# d-cube.net
KiCad netlist of a schematic drawn in EAGLE
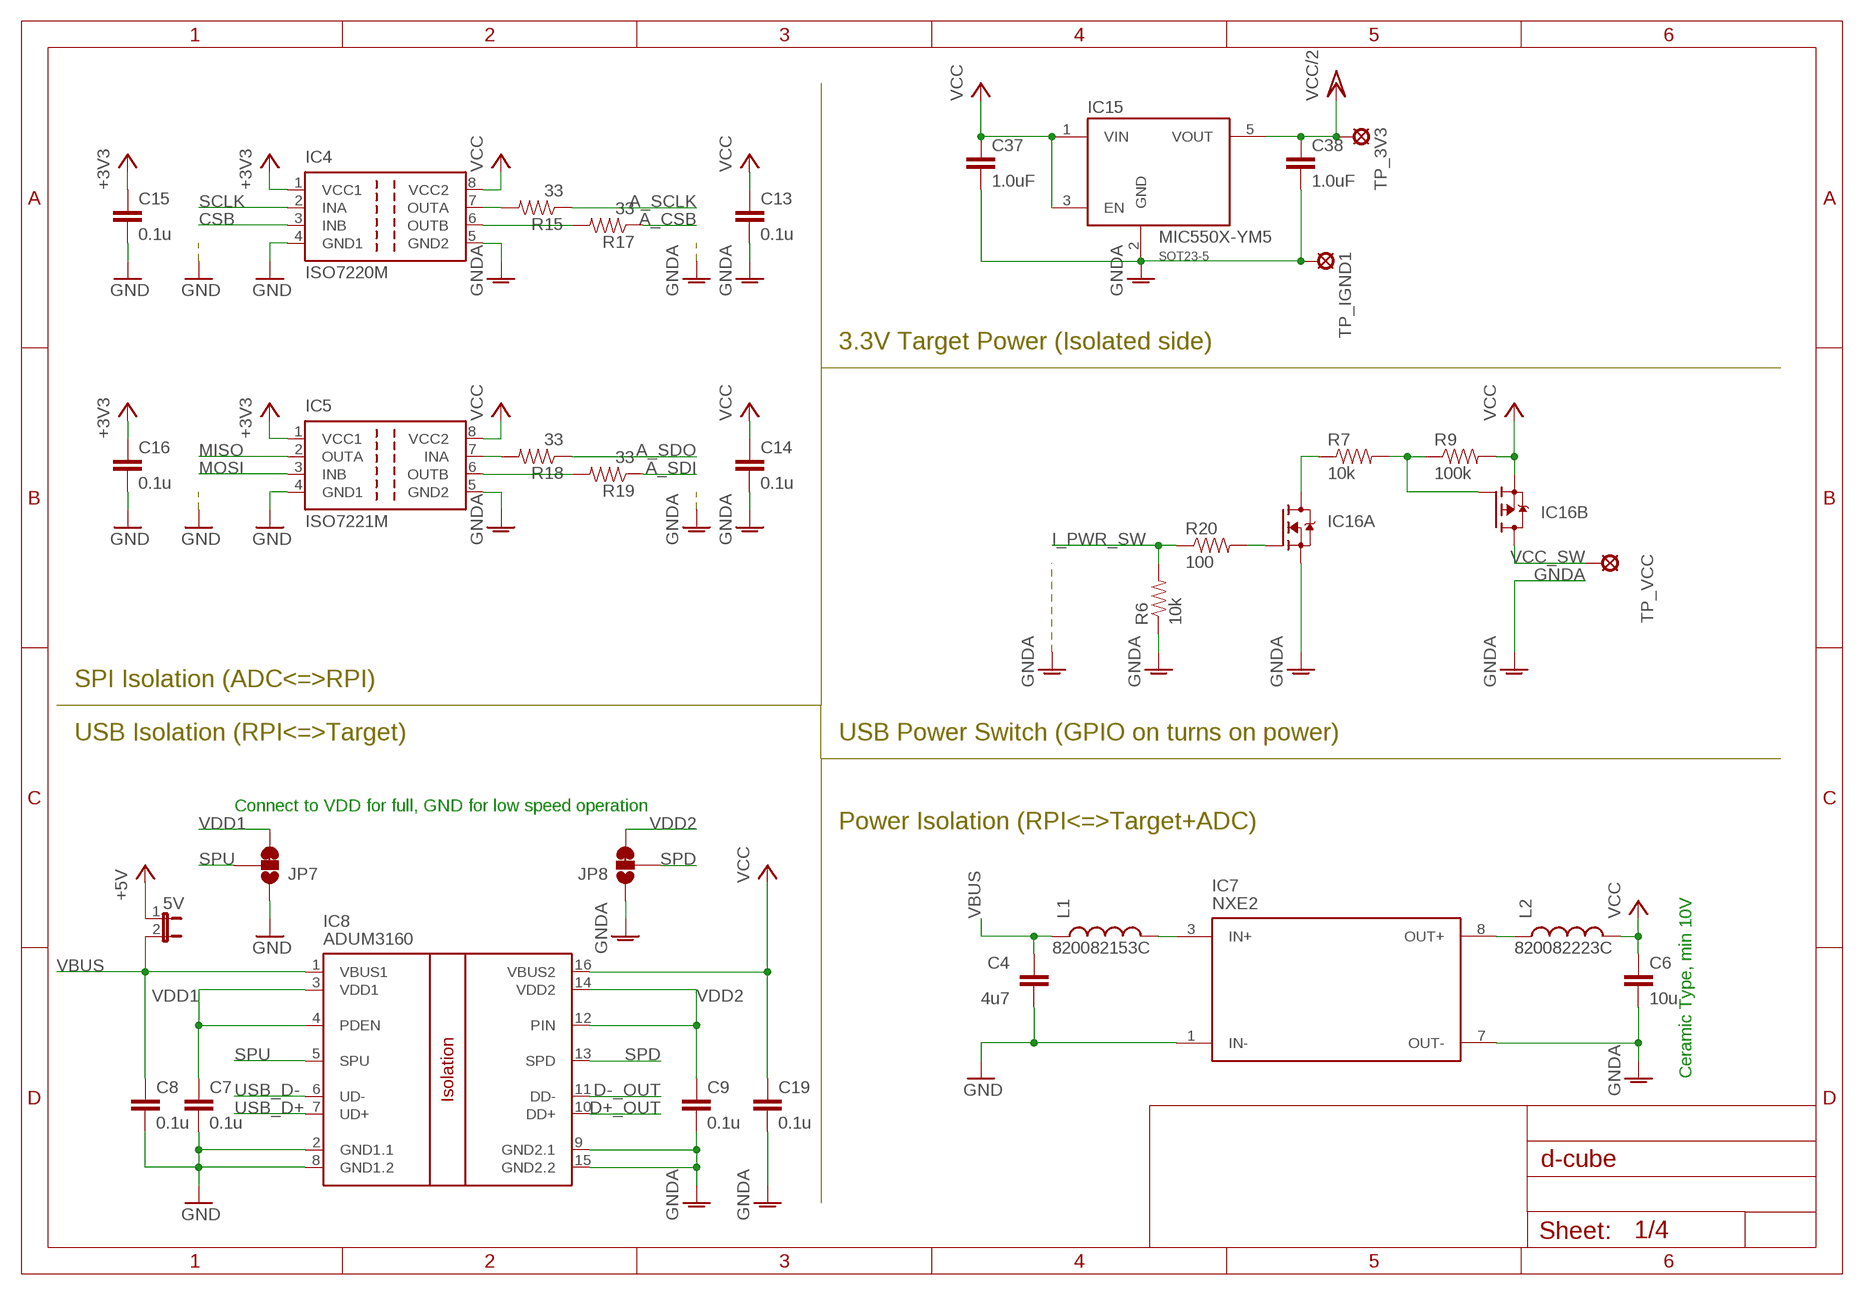
[diagram p0: schematic, sheet 1]
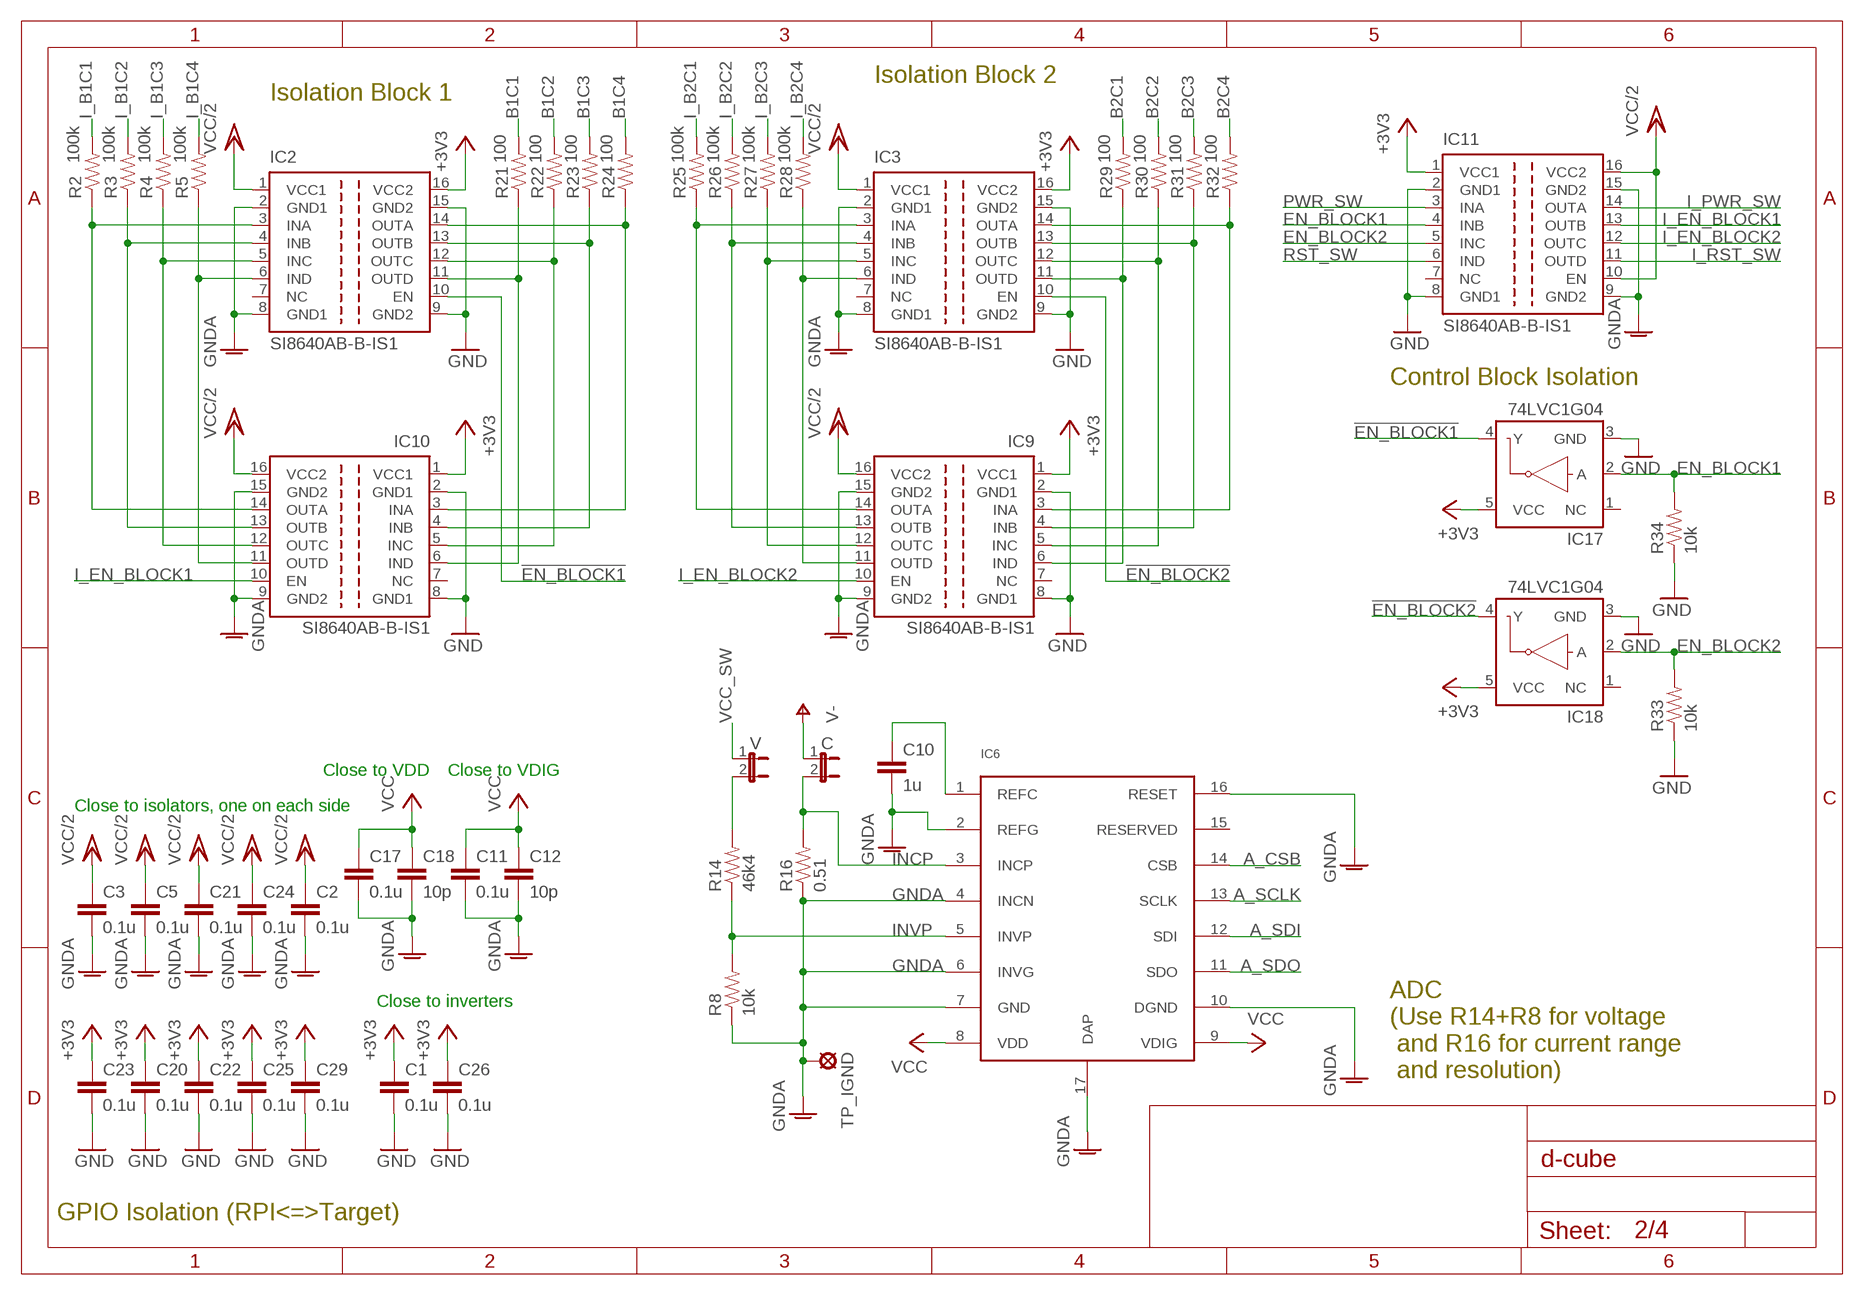
[diagram p1: schematic, sheet 2]
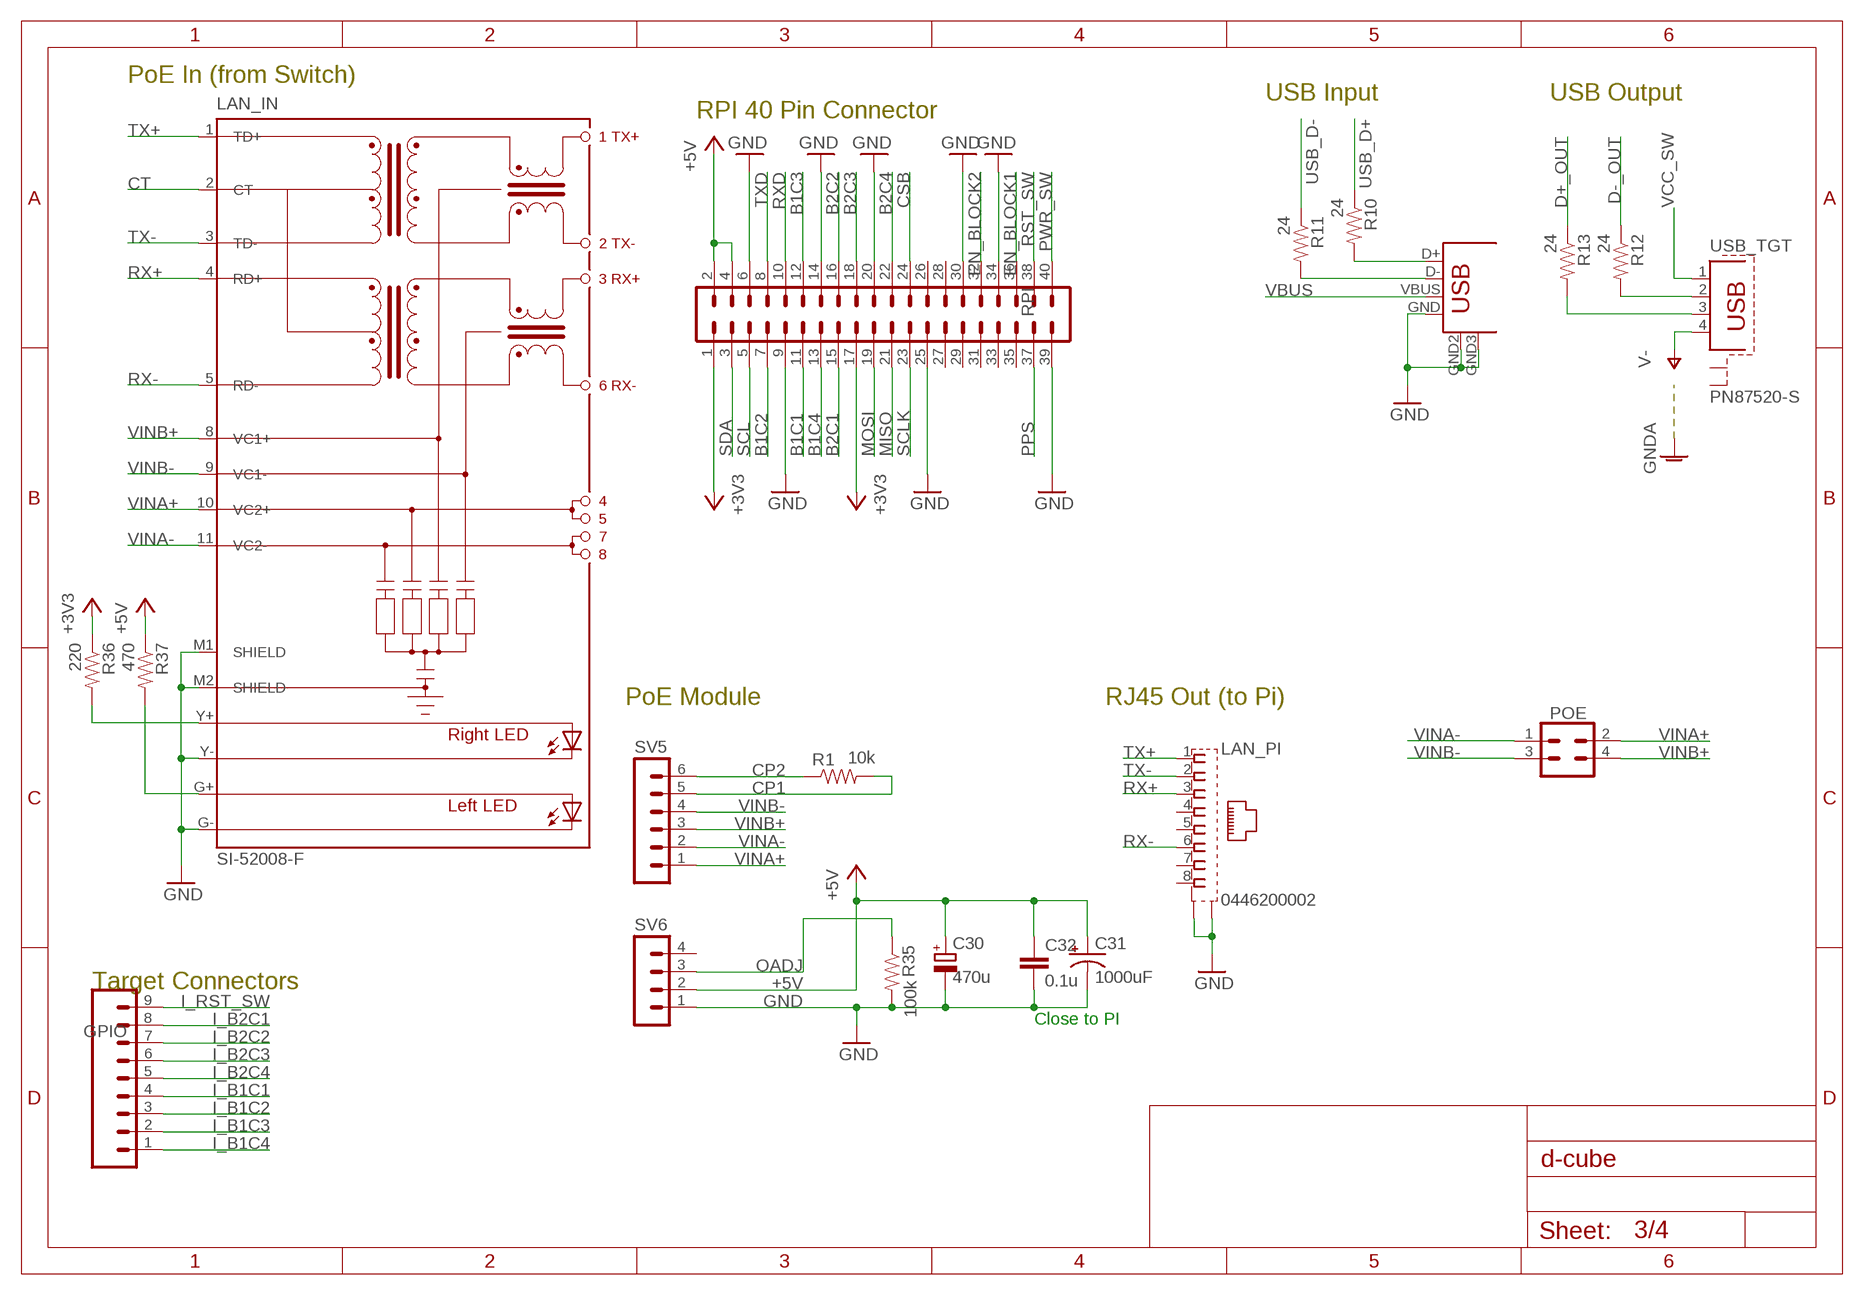
[diagram p2: schematic, sheet 3]
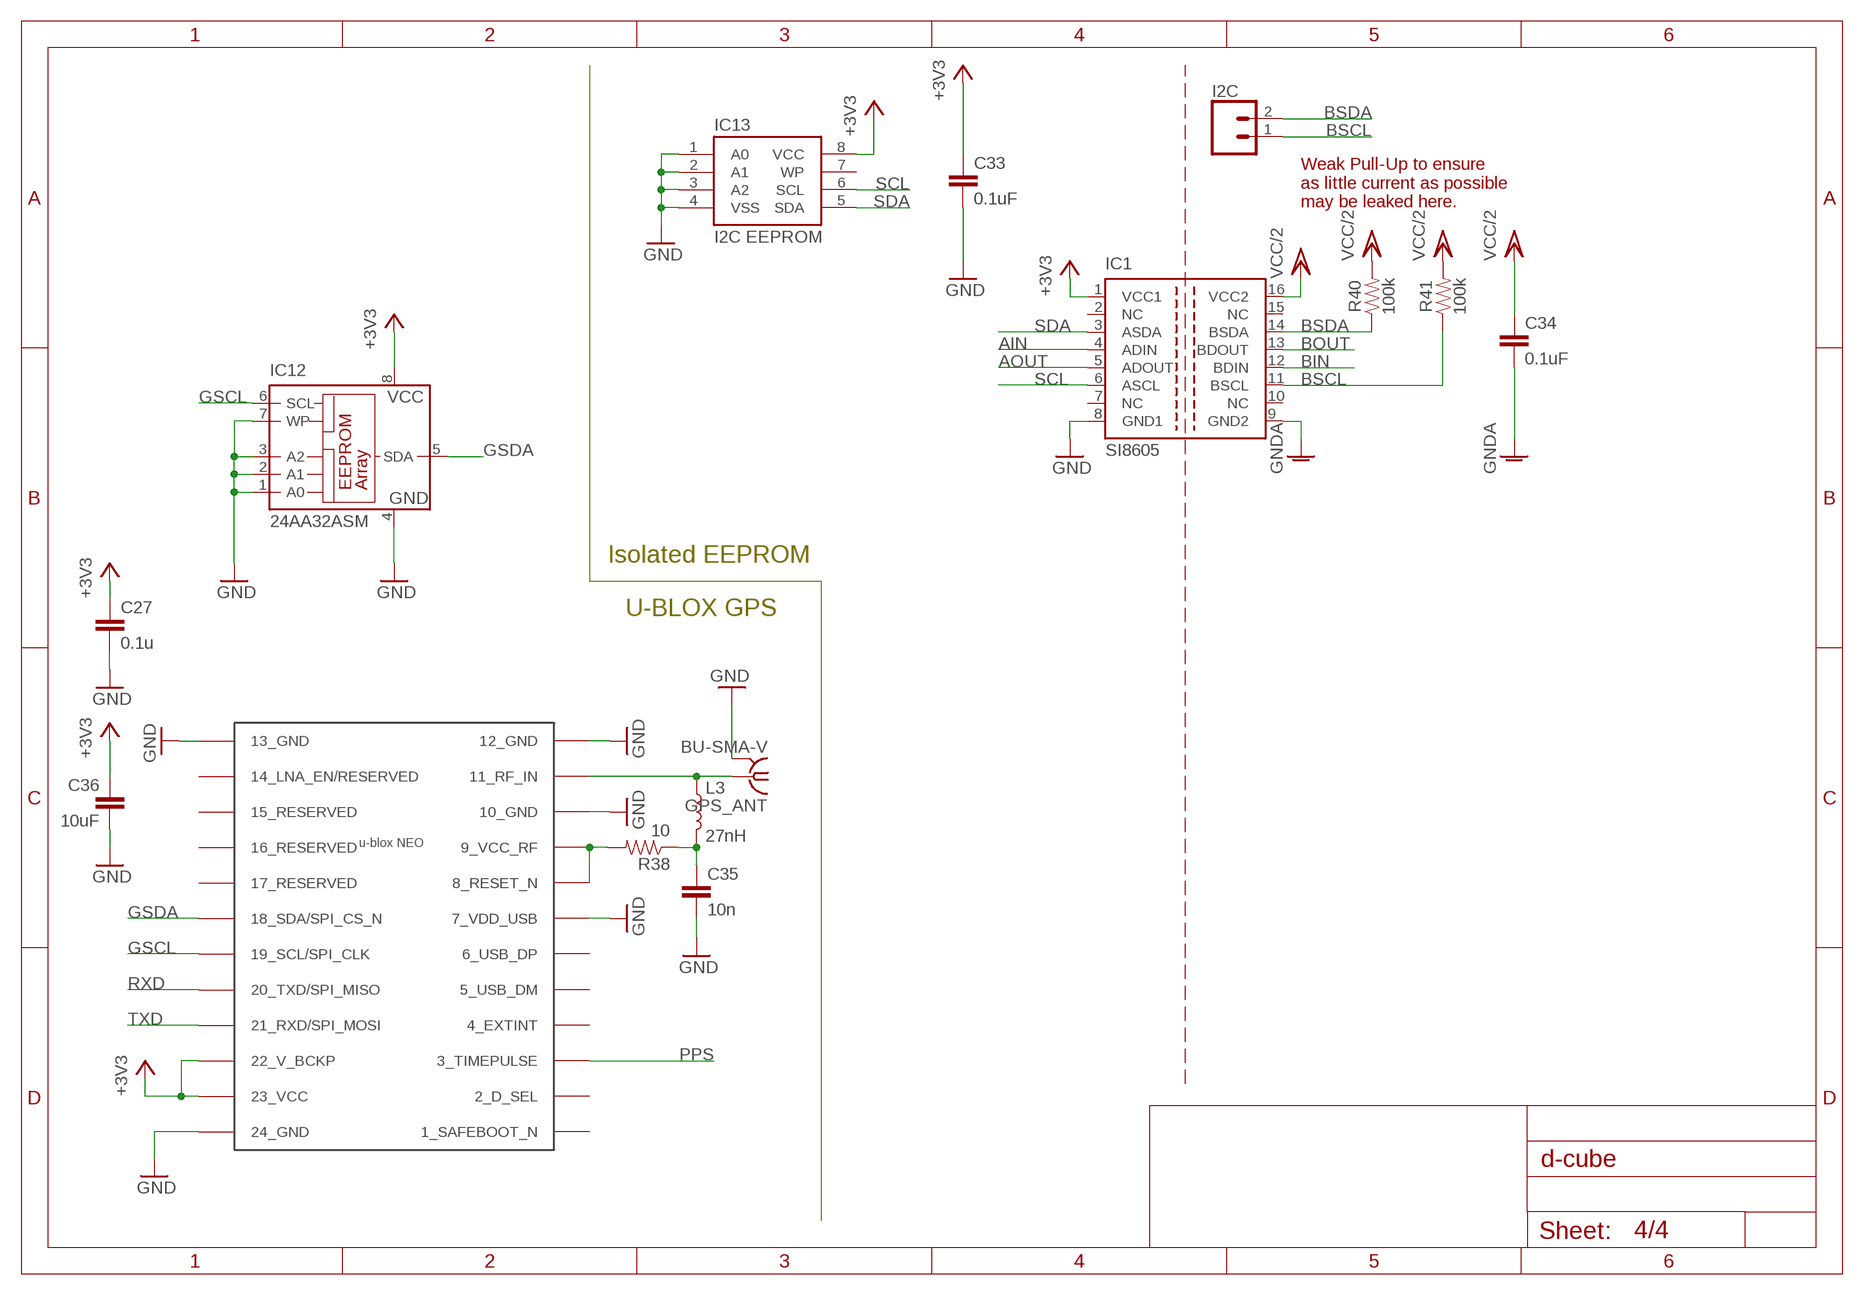
[diagram p3: schematic, sheet 4]

(export (version "E")
  (design (tool "Eeschema 10.0.6"))
  (components
    (comp (ref "C")
      (value "JP1E")
      (footprint "eagle-import:JP1")
      (libsource (lib "eagle-import") (part "JP1E"))
    )
    (comp (ref "C1")
      (value "0.1u")
      (footprint "eagle-import:0402-CAP")
      (libsource (lib "eagle-import") (part "CAP0402-CAP"))
    )
    (comp (ref "C2")
      (value "0.1u")
      (footprint "eagle-import:0402-CAP")
      (libsource (lib "eagle-import") (part "CAP0402-CAP"))
    )
    (comp (ref "C3")
      (value "0.1u")
      (footprint "eagle-import:0402-CAP")
      (libsource (lib "eagle-import") (part "CAP0402-CAP"))
    )
    (comp (ref "C5")
      (value "0.1u")
      (footprint "eagle-import:0402-CAP")
      (libsource (lib "eagle-import") (part "CAP0402-CAP"))
    )
    (comp (ref "C10")
      (value "1u")
      (footprint "eagle-import:0402-CAP")
      (libsource (lib "eagle-import") (part "CAP0402-CAP"))
    )
    (comp (ref "C11")
      (value "0.1u")
      (footprint "eagle-import:0402-CAP")
      (libsource (lib "eagle-import") (part "CAP0402-CAP"))
    )
    (comp (ref "C12")
      (value "10p")
      (footprint "eagle-import:0402-CAP")
      (libsource (lib "eagle-import") (part "CAP0402-CAP"))
    )
    (comp (ref "C17")
      (value "0.1u")
      (footprint "eagle-import:0402-CAP")
      (libsource (lib "eagle-import") (part "CAP0402-CAP"))
    )
    (comp (ref "C18")
      (value "10p")
      (footprint "eagle-import:0402-CAP")
      (libsource (lib "eagle-import") (part "CAP0402-CAP"))
    )
    (comp (ref "C20")
      (value "0.1u")
      (footprint "eagle-import:0402-CAP")
      (libsource (lib "eagle-import") (part "CAP0402-CAP"))
    )
    (comp (ref "C21")
      (value "0.1u")
      (footprint "eagle-import:0402-CAP")
      (libsource (lib "eagle-import") (part "CAP0402-CAP"))
    )
    (comp (ref "C22")
      (value "0.1u")
      (footprint "eagle-import:0402-CAP")
      (libsource (lib "eagle-import") (part "CAP0402-CAP"))
    )
    (comp (ref "C23")
      (value "0.1u")
      (footprint "eagle-import:0402-CAP")
      (libsource (lib "eagle-import") (part "CAP0402-CAP"))
    )
    (comp (ref "C24")
      (value "0.1u")
      (footprint "eagle-import:0402-CAP")
      (libsource (lib "eagle-import") (part "CAP0402-CAP"))
    )
    (comp (ref "C25")
      (value "0.1u")
      (footprint "eagle-import:0402-CAP")
      (libsource (lib "eagle-import") (part "CAP0402-CAP"))
    )
    (comp (ref "C26")
      (value "0.1u")
      (footprint "eagle-import:0402-CAP")
      (libsource (lib "eagle-import") (part "CAP0402-CAP"))
    )
    (comp (ref "C29")
      (value "0.1u")
      (footprint "eagle-import:0402-CAP")
      (libsource (lib "eagle-import") (part "CAP0402-CAP"))
    )
    (comp (ref "IC2")
      (value "SI8640AB-B-IS1")
      (footprint "eagle-import:SO-16")
      (libsource (lib "eagle-import") (part "SI8640AB-B-IS1"))
    )
    (comp (ref "IC3")
      (value "SI8640AB-B-IS1")
      (footprint "eagle-import:SO-16")
      (libsource (lib "eagle-import") (part "SI8640AB-B-IS1"))
    )
    (comp (ref "IC6")
      (value "LMP92064")
      (footprint "eagle-import:WSON-16")
      (libsource (lib "eagle-import") (part "LMP92064"))
    )
    (comp (ref "IC9")
      (value "SI8640AB-B-IS1")
      (footprint "eagle-import:SO-16")
      (libsource (lib "eagle-import") (part "SI8640AB-B-IS1"))
    )
    (comp (ref "IC10")
      (value "SI8640AB-B-IS1")
      (footprint "eagle-import:SO-16")
      (libsource (lib "eagle-import") (part "SI8640AB-B-IS1"))
    )
    (comp (ref "IC11")
      (value "SI8640AB-B-IS1")
      (footprint "eagle-import:SO-16")
      (libsource (lib "eagle-import") (part "SI8640AB-B-IS1"))
    )
    (comp (ref "IC17")
      (value "74LVC1G04")
      (footprint "eagle-import:SOT353")
      (libsource (lib "eagle-import") (part "INVERTER_SOT353-5"))
    )
    (comp (ref "IC18")
      (value "74LVC1G04")
      (footprint "eagle-import:SOT353")
      (libsource (lib "eagle-import") (part "INVERTER_SOT353-5"))
    )
    (comp (ref "R2")
      (value "100k")
      (footprint "eagle-import:0402-RES")
      (libsource (lib "eagle-import") (part "RESISTOR0402-RES"))
    )
    (comp (ref "R3")
      (value "100k")
      (footprint "eagle-import:0402-RES")
      (libsource (lib "eagle-import") (part "RESISTOR0402-RES"))
    )
    (comp (ref "R4")
      (value "100k")
      (footprint "eagle-import:0402-RES")
      (libsource (lib "eagle-import") (part "RESISTOR0402-RES"))
    )
    (comp (ref "R5")
      (value "100k")
      (footprint "eagle-import:0402-RES")
      (libsource (lib "eagle-import") (part "RESISTOR0402-RES"))
    )
    (comp (ref "R8")
      (value "10k")
      (footprint "eagle-import:0805")
      (libsource (lib "eagle-import") (part "RESISTOR0805-RES"))
    )
    (comp (ref "R14")
      (value "46k4")
      (footprint "eagle-import:0805")
      (libsource (lib "eagle-import") (part "RESISTOR0805-RES"))
    )
    (comp (ref "R16")
      (value "0.51")
      (footprint "eagle-import:1206")
      (libsource (lib "eagle-import") (part "RESISTOR1206"))
    )
    (comp (ref "R21")
      (value "100")
      (footprint "eagle-import:0402-RES")
      (libsource (lib "eagle-import") (part "RESISTOR0402-RES"))
    )
    (comp (ref "R22")
      (value "100")
      (footprint "eagle-import:0402-RES")
      (libsource (lib "eagle-import") (part "RESISTOR0402-RES"))
    )
    (comp (ref "R23")
      (value "100")
      (footprint "eagle-import:0402-RES")
      (libsource (lib "eagle-import") (part "RESISTOR0402-RES"))
    )
    (comp (ref "R24")
      (value "100")
      (footprint "eagle-import:0402-RES")
      (libsource (lib "eagle-import") (part "RESISTOR0402-RES"))
    )
    (comp (ref "R25")
      (value "100k")
      (footprint "eagle-import:0402-RES")
      (libsource (lib "eagle-import") (part "RESISTOR0402-RES"))
    )
    (comp (ref "R26")
      (value "100k")
      (footprint "eagle-import:0402-RES")
      (libsource (lib "eagle-import") (part "RESISTOR0402-RES"))
    )
    (comp (ref "R27")
      (value "100k")
      (footprint "eagle-import:0402-RES")
      (libsource (lib "eagle-import") (part "RESISTOR0402-RES"))
    )
    (comp (ref "R28")
      (value "100k")
      (footprint "eagle-import:0402-RES")
      (libsource (lib "eagle-import") (part "RESISTOR0402-RES"))
    )
    (comp (ref "R29")
      (value "100")
      (footprint "eagle-import:0402-RES")
      (libsource (lib "eagle-import") (part "RESISTOR0402-RES"))
    )
    (comp (ref "R30")
      (value "100")
      (footprint "eagle-import:0402-RES")
      (libsource (lib "eagle-import") (part "RESISTOR0402-RES"))
    )
    (comp (ref "R31")
      (value "100")
      (footprint "eagle-import:0402-RES")
      (libsource (lib "eagle-import") (part "RESISTOR0402-RES"))
    )
    (comp (ref "R32")
      (value "100")
      (footprint "eagle-import:0402-RES")
      (libsource (lib "eagle-import") (part "RESISTOR0402-RES"))
    )
    (comp (ref "R33")
      (value "10k")
      (footprint "eagle-import:0402-RES")
      (libsource (lib "eagle-import") (part "RESISTOR0402-RES"))
    )
    (comp (ref "R34")
      (value "10k")
      (footprint "eagle-import:0402-RES")
      (libsource (lib "eagle-import") (part "RESISTOR0402-RES"))
    )
    (comp (ref "TP_IGND")
      (value "LSP10")
      (footprint "eagle-import:LSP10")
      (libsource (lib "eagle-import") (part "LSP10"))
    )
    (comp (ref "V")
      (value "JP1E")
      (footprint "eagle-import:JP1")
      (libsource (lib "eagle-import") (part "JP1E"))
    )
    (comp (ref "5V")
      (value "JP1E")
      (footprint "eagle-import:JP1")
      (libsource (lib "eagle-import") (part "JP1E"))
    )
    (comp (ref "C4")
      (value "4u7")
      (footprint "eagle-import:0805")
      (libsource (lib "eagle-import") (part "CAP0805"))
    )
    (comp (ref "C6")
      (value "10u")
      (footprint "eagle-import:0805")
      (libsource (lib "eagle-import") (part "CAP0805"))
    )
    (comp (ref "C7")
      (value "0.1u")
      (footprint "eagle-import:0402-CAP")
      (libsource (lib "eagle-import") (part "CAP0402-CAP"))
    )
    (comp (ref "C8")
      (value "0.1u")
      (footprint "eagle-import:0402-CAP")
      (libsource (lib "eagle-import") (part "CAP0402-CAP"))
    )
    (comp (ref "C9")
      (value "0.1u")
      (footprint "eagle-import:0402-CAP")
      (libsource (lib "eagle-import") (part "CAP0402-CAP"))
    )
    (comp (ref "C13")
      (value "0.1u")
      (footprint "eagle-import:0402-CAP")
      (libsource (lib "eagle-import") (part "CAP0402-CAP"))
    )
    (comp (ref "C14")
      (value "0.1u")
      (footprint "eagle-import:0402-CAP")
      (libsource (lib "eagle-import") (part "CAP0402-CAP"))
    )
    (comp (ref "C15")
      (value "0.1u")
      (footprint "eagle-import:0402-CAP")
      (libsource (lib "eagle-import") (part "CAP0402-CAP"))
    )
    (comp (ref "C16")
      (value "0.1u")
      (footprint "eagle-import:0402-CAP")
      (libsource (lib "eagle-import") (part "CAP0402-CAP"))
    )
    (comp (ref "C19")
      (value "0.1u")
      (footprint "eagle-import:0402-CAP")
      (libsource (lib "eagle-import") (part "CAP0402-CAP"))
    )
    (comp (ref "C37")
      (value "1.0uF")
      (footprint "eagle-import:0805")
      (libsource (lib "eagle-import") (part "1.0UF-0805-25V-10%"))
    )
    (comp (ref "C38")
      (value "1.0uF")
      (footprint "eagle-import:0805")
      (libsource (lib "eagle-import") (part "1.0UF-0805-25V-10%"))
    )
    (comp (ref "IC4")
      (value "ISO7220M")
      (footprint "eagle-import:SO-08")
      (fields (field (name "MPN") "ISO7220MD"))
      (libsource (lib "eagle-import") (part "ISO7220M"))
    )
    (comp (ref "IC5")
      (value "ISO7221M")
      (footprint "eagle-import:SO-08")
      (fields (field (name "MPN") "ISO7221MD"))
      (libsource (lib "eagle-import") (part "ISO7221M"))
    )
    (comp (ref "IC7")
      (value "NXE2")
      (footprint "eagle-import:NXE2")
      (libsource (lib "eagle-import") (part "NXE2"))
    )
    (comp (ref "IC8")
      (value "ADUM3160")
      (footprint "eagle-import:SO-16W")
      (libsource (lib "eagle-import") (part "ADUM3160"))
    )
    (comp (ref "IC15")
      (value "MIC550X-YM5")
      (footprint "eagle-import:SOT23-5-DBV")
      (fields (field (name "PACKAGE") "SOT23-5"))
      (libsource (lib "eagle-import") (part "MIC550X-YM5"))
    )
    (comp (ref "IC16")
      (value "COMPLEMENTARY")
      (footprint "eagle-import:SOT-363")
      (libsource (lib "eagle-import") (part "COMPLEMENTARY"))
    )
    (comp (ref "JP7")
      (value "JUMPER-PAD-3-2OF3_NC_BY_TRACE_LARGE")
      (footprint "eagle-import:PAD-JUMPER-3-2OF3_NC_BY_TRACE_YES_SILK_LARGE")
      (libsource (lib "eagle-import") (part "JUMPER-PAD-3-2OF3_NC_BY_TRACE_LARGE"))
    )
    (comp (ref "JP8")
      (value "JUMPER-PAD-3-2OF3_NC_BY_TRACE_LARGE")
      (footprint "eagle-import:PAD-JUMPER-3-2OF3_NC_BY_TRACE_YES_SILK_LARGE")
      (libsource (lib "eagle-import") (part "JUMPER-PAD-3-2OF3_NC_BY_TRACE_LARGE"))
    )
    (comp (ref "L1")
      (value "820082153C")
      (footprint "eagle-import:8200")
      (libsource (lib "eagle-import") (part "820082153C"))
    )
    (comp (ref "L2")
      (value "820082223C")
      (footprint "eagle-import:8200")
      (libsource (lib "eagle-import") (part "820082223C"))
    )
    (comp (ref "R6")
      (value "10k")
      (footprint "eagle-import:0402-RES")
      (libsource (lib "eagle-import") (part "RESISTOR0402-RES"))
    )
    (comp (ref "R7")
      (value "10k")
      (footprint "eagle-import:0402-RES")
      (libsource (lib "eagle-import") (part "RESISTOR0402-RES"))
    )
    (comp (ref "R9")
      (value "100k")
      (footprint "eagle-import:0402-RES")
      (libsource (lib "eagle-import") (part "RESISTOR0402-RES"))
    )
    (comp (ref "R15")
      (value "33")
      (footprint "eagle-import:0402-RES")
      (libsource (lib "eagle-import") (part "RESISTOR0402-RES"))
    )
    (comp (ref "R17")
      (value "33")
      (footprint "eagle-import:0402-RES")
      (libsource (lib "eagle-import") (part "RESISTOR0402-RES"))
    )
    (comp (ref "R18")
      (value "33")
      (footprint "eagle-import:0402-RES")
      (libsource (lib "eagle-import") (part "RESISTOR0402-RES"))
    )
    (comp (ref "R19")
      (value "33")
      (footprint "eagle-import:0402-RES")
      (libsource (lib "eagle-import") (part "RESISTOR0402-RES"))
    )
    (comp (ref "R20")
      (value "100")
      (footprint "eagle-import:0402-RES")
      (libsource (lib "eagle-import") (part "RESISTOR0402-RES"))
    )
    (comp (ref "TP_3V3")
      (value "LSP10")
      (footprint "eagle-import:LSP10")
      (libsource (lib "eagle-import") (part "LSP10"))
    )
    (comp (ref "TP_IGND1")
      (value "LSP10")
      (footprint "eagle-import:LSP10")
      (libsource (lib "eagle-import") (part "LSP10"))
    )
    (comp (ref "TP_VCC")
      (value "LSP10")
      (footprint "eagle-import:LSP10")
      (libsource (lib "eagle-import") (part "LSP10"))
    )
    (comp (ref "C27")
      (value "0.1u")
      (footprint "eagle-import:0402-CAP")
      (libsource (lib "eagle-import") (part "CAP0402-CAP"))
    )
    (comp (ref "C33")
      (value "0.1uF")
      (footprint "eagle-import:0402")
      (libsource (lib "eagle-import") (part "0.1UF-0402-16V-10%"))
    )
    (comp (ref "C34")
      (value "0.1uF")
      (footprint "eagle-import:0402")
      (libsource (lib "eagle-import") (part "0.1UF-0402-16V-10%"))
    )
    (comp (ref "C35")
      (value "10n")
      (footprint "eagle-import:0805")
      (libsource (lib "eagle-import") (part "CAP0805"))
    )
    (comp (ref "C36")
      (value "10uF")
      (footprint "eagle-import:0805")
      (libsource (lib "eagle-import") (part "10UF-0805-10V-10%"))
    )
    (comp (ref "GPS_ANT")
      (value "BU-SMA-V")
      (footprint "eagle-import:BU-SMA-V")
      (libsource (lib "eagle-import") (part "BU-SMA-V"))
    )
    (comp (ref "I2C")
      (value "CONN_021X02_NO_SILK")
      (footprint "eagle-import:1X02_NO_SILK")
      (libsource (lib "eagle-import") (part "CONN_021X02_NO_SILK"))
    )
    (comp (ref "IC1")
      (value "SI8605")
      (footprint "eagle-import:SO-16")
      (libsource (lib "eagle-import") (part "SI8605"))
    )
    (comp (ref "IC12")
      (value "24AA32ASM")
      (footprint "eagle-import:SO-08M")
      (fields (field (name "MF") "MICROCHIP") (field (name "MPN") "24AA32A-I/SN"))
      (libsource (lib "eagle-import") (part "24SMAA32A"))
    )
    (comp (ref "IC13")
      (value "I2C EEPROM")
      (footprint "eagle-import:SO08-EIAJ")
      (libsource (lib "eagle-import") (part "EEPROM-I2CEIAJ"))
    )
    (comp (ref "IC14")
      (value "NEO-M8")
      (footprint "eagle-import:NEO-M8")
      (libsource (lib "eagle-import") (part "NEO-M8"))
    )
    (comp (ref "L3")
      (value "27nH")
      (footprint "eagle-import:0402")
      (libsource (lib "eagle-import") (part "INDUCTOR-0402-3.9NH"))
    )
    (comp (ref "R38")
      (value "10")
      (footprint "eagle-import:0402-RES")
      (libsource (lib "eagle-import") (part "RESISTOR0402-RES"))
    )
    (comp (ref "R40")
      (value "100k")
      (footprint "eagle-import:0402")
      (libsource (lib "eagle-import") (part "RESISTOR0402"))
    )
    (comp (ref "R41")
      (value "100k")
      (footprint "eagle-import:0402")
      (libsource (lib "eagle-import") (part "RESISTOR0402"))
    )
    (comp (ref "C30")
      (value "470u")
      (footprint "eagle-import:CT7343")
      (libsource (lib "eagle-import") (part "CPOL-EUCT7343"))
    )
    (comp (ref "C31")
      (value "1000uF")
      (footprint "eagle-import:PANASONIC_G")
      (libsource (lib "eagle-import") (part "560UF-PANASONIC_G-25V-20%"))
    )
    (comp (ref "C32")
      (value "0.1u")
      (footprint "eagle-import:0805")
      (libsource (lib "eagle-import") (part "CAP0805"))
    )
    (comp (ref "GPIO")
      (value "CONN_09NO_SILK")
      (footprint "eagle-import:1X09_NO_SILK")
      (libsource (lib "eagle-import") (part "CONN_09NO_SILK"))
    )
    (comp (ref "LAN_IN")
      (value "SI-52008-F")
      (footprint "eagle-import:POE")
      (libsource (lib "eagle-import") (part "SI-52008-F"))
    )
    (comp (ref "LAN_PI")
      (value "0446200002")
      (footprint "eagle-import:0446200002")
      (fields (field (name "MF") "MOLEX"))
      (libsource (lib "eagle-import") (part "0446200002"))
    )
    (comp (ref "POE")
      (value "CONN_02X2")
      (footprint "eagle-import:2X02_NO_SILK")
      (libsource (lib "eagle-import") (part "CONN_02X2"))
    )
    (comp (ref "R1")
      (value "10k")
      (footprint "eagle-import:0402-RES")
      (libsource (lib "eagle-import") (part "RESISTOR0402-RES"))
    )
    (comp (ref "R10")
      (value "24")
      (footprint "eagle-import:0402-RES")
      (libsource (lib "eagle-import") (part "RESISTOR0402-RES"))
    )
    (comp (ref "R11")
      (value "24")
      (footprint "eagle-import:0402-RES")
      (libsource (lib "eagle-import") (part "RESISTOR0402-RES"))
    )
    (comp (ref "R12")
      (value "24")
      (footprint "eagle-import:0402-RES")
      (libsource (lib "eagle-import") (part "RESISTOR0402-RES"))
    )
    (comp (ref "R13")
      (value "24")
      (footprint "eagle-import:0402-RES")
      (libsource (lib "eagle-import") (part "RESISTOR0402-RES"))
    )
    (comp (ref "R35")
      (value "100k")
      (footprint "eagle-import:0402-RES")
      (libsource (lib "eagle-import") (part "RESISTOR0402-RES"))
    )
    (comp (ref "R36")
      (value "220")
      (footprint "eagle-import:0402-RES")
      (libsource (lib "eagle-import") (part "RESISTOR0402-RES"))
    )
    (comp (ref "R37")
      (value "470")
      (footprint "eagle-import:0402-RES")
      (libsource (lib "eagle-import") (part "RESISTOR0402-RES"))
    )
    (comp (ref "RPI")
      (value "MA20-2")
      (footprint "eagle-import:MA20-2")
      (libsource (lib "eagle-import") (part "MA20-2"))
    )
    (comp (ref "SV5")
      (value "MA06-1")
      (footprint "eagle-import:MA06-1")
      (libsource (lib "eagle-import") (part "MA06-1"))
    )
    (comp (ref "SV6")
      (value "MA04-1")
      (footprint "eagle-import:MA04-1")
      (libsource (lib "eagle-import") (part "MA04-1"))
    )
    (comp (ref "USB_PI")
      (value "USB+SHIELDUSB-A-H-S")
      (footprint "eagle-import:USB-A-H")
      (libsource (lib "eagle-import") (part "USB+SHIELDUSB-A-H-S"))
    )
    (comp (ref "USB_TGT")
      (value "PN87520-S")
      (footprint "eagle-import:PN87520-S")
      (libsource (lib "eagle-import") (part "PN87520-S"))
    )
  )
  (nets
    (net (code "1") (name "+3V3") (class "Default")
      (node (ref "C1") (pin "1") (pinfunction "1_1") (pintype "passive"))
      (node (ref "C15") (pin "1") (pinfunction "1_1") (pintype "passive"))
      (node (ref "C16") (pin "1") (pinfunction "1_1") (pintype "passive"))
      (node (ref "C20") (pin "1") (pinfunction "1_1") (pintype "passive"))
      (node (ref "C22") (pin "1") (pinfunction "1_1") (pintype "passive"))
      (node (ref "C23") (pin "1") (pinfunction "1_1") (pintype "passive"))
      (node (ref "C25") (pin "1") (pinfunction "1_1") (pintype "passive"))
      (node (ref "C26") (pin "1") (pinfunction "1_1") (pintype "passive"))
      (node (ref "C27") (pin "1") (pinfunction "1_1") (pintype "passive"))
      (node (ref "C29") (pin "1") (pinfunction "1_1") (pintype "passive"))
      (node (ref "C33") (pin "1") (pinfunction "1_1") (pintype "passive"))
      (node (ref "C36") (pin "1") (pinfunction "1_1") (pintype "passive"))
      (node (ref "IC1") (pin "1") (pinfunction "VCC1_1") (pintype "power_in"))
      (node (ref "IC10") (pin "1") (pinfunction "VCC1_1") (pintype "power_in"))
      (node (ref "IC11") (pin "1") (pinfunction "VCC1_1") (pintype "power_in"))
      (node (ref "IC12") (pin "8") (pinfunction "VCC_8") (pintype "power_in"))
      (node (ref "IC13") (pin "8") (pinfunction "VCC_8") (pintype "power_in"))
      (node (ref "IC14") (pin "22") (pinfunction "22_V_BCKP_22") (pintype "bidirectional"))
      (node (ref "IC14") (pin "23") (pinfunction "23_VCC_23") (pintype "bidirectional"))
      (node (ref "IC17") (pin "5") (pinfunction "VCC_5") (pintype "bidirectional"))
      (node (ref "IC18") (pin "5") (pinfunction "VCC_5") (pintype "bidirectional"))
      (node (ref "IC2") (pin "16") (pinfunction "VCC2_16") (pintype "power_in"))
      (node (ref "IC3") (pin "16") (pinfunction "VCC2_16") (pintype "power_in"))
      (node (ref "IC4") (pin "1") (pinfunction "VCC1_1") (pintype "power_in"))
      (node (ref "IC5") (pin "1") (pinfunction "VCC1_1") (pintype "power_in"))
      (node (ref "IC9") (pin "1") (pinfunction "VCC1_1") (pintype "power_in"))
      (node (ref "R36") (pin "1") (pinfunction "1_1") (pintype "passive"))
      (node (ref "RPI") (pin "1") (pinfunction "1_1") (pintype "passive"))
      (node (ref "RPI") (pin "17") (pinfunction "17_17") (pintype "passive"))
    )
    (net (code "2") (name "+5V") (class "Default")
      (node (ref "5V") (pin "1") (pinfunction "1_1") (pintype "passive"))
      (node (ref "C30") (pin "+") (pinfunction "+_+") (pintype "passive"))
      (node (ref "C31") (pin "+") (pinfunction "+_+") (pintype "passive"))
      (node (ref "C32") (pin "1") (pinfunction "1_1") (pintype "passive"))
      (node (ref "R37") (pin "1") (pinfunction "1_1") (pintype "passive"))
      (node (ref "RPI") (pin "2") (pinfunction "2_2") (pintype "passive"))
      (node (ref "RPI") (pin "4") (pinfunction "4_4") (pintype "passive"))
      (node (ref "SV6") (pin "2") (pinfunction "2_2") (pintype "passive"))
    )
    (net (code "3") (name "AIN") (class "Default")
      (node (ref "IC1") (pin "4") (pinfunction "ADIN_4") (pintype "input"))
    )
    (net (code "4") (name "AOUT") (class "Default")
      (node (ref "IC1") (pin "5") (pinfunction "ADOUT_5") (pintype "input"))
    )
    (net (code "5") (name "A_CSB") (class "Default")
      (node (ref "IC6") (pin "14") (pinfunction "CSB_14") (pintype "input"))
      (node (ref "R17") (pin "1") (pinfunction "1_1") (pintype "passive"))
    )
    (net (code "6") (name "A_SCLK") (class "Default")
      (node (ref "IC6") (pin "13") (pinfunction "SCLK_13") (pintype "input"))
      (node (ref "R15") (pin "1") (pinfunction "1_1") (pintype "passive"))
    )
    (net (code "7") (name "A_SDI") (class "Default")
      (node (ref "IC6") (pin "12") (pinfunction "SDI_12") (pintype "input"))
      (node (ref "R19") (pin "1") (pinfunction "1_1") (pintype "passive"))
    )
    (net (code "8") (name "A_SDO") (class "Default")
      (node (ref "IC6") (pin "11") (pinfunction "SDO_11") (pintype "output"))
      (node (ref "R18") (pin "1") (pinfunction "1_1") (pintype "passive"))
    )
    (net (code "9") (name "B1C1") (class "Default")
      (node (ref "R21") (pin "2") (pinfunction "2_2") (pintype "passive"))
      (node (ref "RPI") (pin "11") (pinfunction "11_11") (pintype "passive"))
    )
    (net (code "10") (name "B1C2") (class "Default")
      (node (ref "R22") (pin "2") (pinfunction "2_2") (pintype "passive"))
      (node (ref "RPI") (pin "7") (pinfunction "7_7") (pintype "passive"))
    )
    (net (code "11") (name "B1C3") (class "Default")
      (node (ref "R23") (pin "2") (pinfunction "2_2") (pintype "passive"))
      (node (ref "RPI") (pin "12") (pinfunction "12_12") (pintype "passive"))
    )
    (net (code "12") (name "B1C4") (class "Default")
      (node (ref "R24") (pin "2") (pinfunction "2_2") (pintype "passive"))
      (node (ref "RPI") (pin "13") (pinfunction "13_13") (pintype "passive"))
    )
    (net (code "13") (name "B2C1") (class "Default")
      (node (ref "R29") (pin "2") (pinfunction "2_2") (pintype "passive"))
      (node (ref "RPI") (pin "15") (pinfunction "15_15") (pintype "passive"))
    )
    (net (code "14") (name "B2C2") (class "Default")
      (node (ref "R30") (pin "2") (pinfunction "2_2") (pintype "passive"))
      (node (ref "RPI") (pin "16") (pinfunction "16_16") (pintype "passive"))
    )
    (net (code "15") (name "B2C3") (class "Default")
      (node (ref "R31") (pin "2") (pinfunction "2_2") (pintype "passive"))
      (node (ref "RPI") (pin "18") (pinfunction "18_18") (pintype "passive"))
    )
    (net (code "16") (name "B2C4") (class "Default")
      (node (ref "R32") (pin "2") (pinfunction "2_2") (pintype "passive"))
      (node (ref "RPI") (pin "22") (pinfunction "22_22") (pintype "passive"))
    )
    (net (code "17") (name "BIN") (class "Default")
      (node (ref "IC1") (pin "12") (pinfunction "BDIN_12") (pintype "input"))
    )
    (net (code "18") (name "BOUT") (class "Default")
      (node (ref "IC1") (pin "13") (pinfunction "BDOUT_13") (pintype "output"))
    )
    (net (code "19") (name "BSCL") (class "Default")
      (node (ref "I2C") (pin "1") (pinfunction "1_1") (pintype "passive"))
      (node (ref "IC1") (pin "11") (pinfunction "BSCL_11") (pintype "bidirectional"))
      (node (ref "R41") (pin "1") (pinfunction "1_1") (pintype "passive"))
    )
    (net (code "20") (name "BSDA") (class "Default")
      (node (ref "I2C") (pin "2") (pinfunction "2_2") (pintype "passive"))
      (node (ref "IC1") (pin "14") (pinfunction "BSDA_14") (pintype "bidirectional"))
      (node (ref "R40") (pin "1") (pinfunction "1_1") (pintype "passive"))
    )
    (net (code "21") (name "CP1") (class "Default")
      (node (ref "R1") (pin "2") (pinfunction "2_2") (pintype "passive"))
      (node (ref "SV5") (pin "5") (pinfunction "5_5") (pintype "passive"))
    )
    (net (code "22") (name "CP2") (class "Default")
      (node (ref "R1") (pin "1") (pinfunction "1_1") (pintype "passive"))
      (node (ref "SV5") (pin "6") (pinfunction "6_6") (pintype "passive"))
    )
    (net (code "23") (name "CSB") (class "Default")
      (node (ref "IC4") (pin "3") (pinfunction "INB_3") (pintype "input"))
      (node (ref "RPI") (pin "24") (pinfunction "24_24") (pintype "passive"))
    )
    (net (code "24") (name "CT") (class "Default")
      (node (ref "LAN_IN") (pin "2") (pinfunction "CT_2") (pintype "input"))
    )
    (net (code "25") (name "D+_OUT") (class "Default")
      (node (ref "IC8") (pin "10") (pinfunction "DD+_10") (pintype "bidirectional"))
      (node (ref "R13") (pin "1") (pinfunction "1_1") (pintype "passive"))
    )
    (net (code "26") (name "D-_OUT") (class "Default")
      (node (ref "IC8") (pin "11") (pinfunction "DD-_11") (pintype "bidirectional"))
      (node (ref "R12") (pin "1") (pinfunction "1_1") (pintype "passive"))
    )
    (net (code "27") (name "EN_BLOCK1") (class "Default")
      (node (ref "IC11") (pin "4") (pinfunction "INB_4") (pintype "input"))
      (node (ref "IC17") (pin "2") (pinfunction "A_2") (pintype "bidirectional"))
      (node (ref "R34") (pin "2") (pinfunction "2_2") (pintype "passive"))
      (node (ref "RPI") (pin "36") (pinfunction "36_36") (pintype "passive"))
    )
    (net (code "28") (name "EN_BLOCK2") (class "Default")
      (node (ref "IC11") (pin "5") (pinfunction "INC_5") (pintype "input"))
      (node (ref "IC18") (pin "2") (pinfunction "A_2") (pintype "bidirectional"))
      (node (ref "R33") (pin "2") (pinfunction "2_2") (pintype "passive"))
      (node (ref "RPI") (pin "32") (pinfunction "32_32") (pintype "passive"))
    )
    (net (code "29") (name "GND") (class "Default")
      (node (ref "C1") (pin "2") (pinfunction "2_2") (pintype "passive"))
      (node (ref "C15") (pin "2") (pinfunction "2_2") (pintype "passive"))
      (node (ref "C16") (pin "2") (pinfunction "2_2") (pintype "passive"))
      (node (ref "C20") (pin "2") (pinfunction "2_2") (pintype "passive"))
      (node (ref "C22") (pin "2") (pinfunction "2_2") (pintype "passive"))
      (node (ref "C23") (pin "2") (pinfunction "2_2") (pintype "passive"))
      (node (ref "C25") (pin "2") (pinfunction "2_2") (pintype "passive"))
      (node (ref "C26") (pin "2") (pinfunction "2_2") (pintype "passive"))
      (node (ref "C27") (pin "2") (pinfunction "2_2") (pintype "passive"))
      (node (ref "C29") (pin "2") (pinfunction "2_2") (pintype "passive"))
      (node (ref "C30") (pin "-") (pinfunction "-_-") (pintype "passive"))
      (node (ref "C31") (pin "-") (pinfunction "-_-") (pintype "passive"))
      (node (ref "C32") (pin "2") (pinfunction "2_2") (pintype "passive"))
      (node (ref "C33") (pin "2") (pinfunction "2_2") (pintype "passive"))
      (node (ref "C35") (pin "2") (pinfunction "2_2") (pintype "passive"))
      (node (ref "C36") (pin "2") (pinfunction "2_2") (pintype "passive"))
      (node (ref "C4") (pin "2") (pinfunction "2_2") (pintype "passive"))
      (node (ref "C7") (pin "2") (pinfunction "2_2") (pintype "passive"))
      (node (ref "C8") (pin "2") (pinfunction "2_2") (pintype "passive"))
      (node (ref "GPS_ANT") (pin "2") (pinfunction "GND_2") (pintype "power_in"))
      (node (ref "IC1") (pin "8") (pinfunction "GND1_8") (pintype "power_in"))
      (node (ref "IC10") (pin "2") (pinfunction "GND1_2") (pintype "power_in"))
      (node (ref "IC10") (pin "8") (pinfunction "GND1_8") (pintype "power_in"))
      (node (ref "IC11") (pin "2") (pinfunction "GND1_2") (pintype "power_in"))
      (node (ref "IC11") (pin "8") (pinfunction "GND1_8") (pintype "power_in"))
      (node (ref "IC12") (pin "1") (pinfunction "A0_1") (pintype "input"))
      (node (ref "IC12") (pin "2") (pinfunction "A1_2") (pintype "input"))
      (node (ref "IC12") (pin "3") (pinfunction "A2_3") (pintype "input"))
      (node (ref "IC12") (pin "4") (pinfunction "GND_4") (pintype "power_in"))
      (node (ref "IC12") (pin "7") (pinfunction "WP_7") (pintype "input"))
      (node (ref "IC13") (pin "1") (pinfunction "A0_1") (pintype "bidirectional"))
      (node (ref "IC13") (pin "2") (pinfunction "A1_2") (pintype "bidirectional"))
      (node (ref "IC13") (pin "3") (pinfunction "A2_3") (pintype "bidirectional"))
      (node (ref "IC13") (pin "4") (pinfunction "VSS_4") (pintype "power_in"))
      (node (ref "IC14") (pin "10") (pinfunction "10_GND_10") (pintype "bidirectional"))
      (node (ref "IC14") (pin "12") (pinfunction "12_GND_12") (pintype "bidirectional"))
      (node (ref "IC14") (pin "13") (pinfunction "13_GND_13") (pintype "bidirectional"))
      (node (ref "IC14") (pin "24") (pinfunction "24_GND_24") (pintype "bidirectional"))
      (node (ref "IC14") (pin "7") (pinfunction "7_VDD_USB_7") (pintype "bidirectional"))
      (node (ref "IC17") (pin "3") (pinfunction "GND_3") (pintype "bidirectional"))
      (node (ref "IC18") (pin "3") (pinfunction "GND_3") (pintype "bidirectional"))
      (node (ref "IC2") (pin "15") (pinfunction "GND2_15") (pintype "power_in"))
      (node (ref "IC2") (pin "9") (pinfunction "GND2_9") (pintype "power_in"))
      (node (ref "IC3") (pin "15") (pinfunction "GND2_15") (pintype "power_in"))
      (node (ref "IC3") (pin "9") (pinfunction "GND2_9") (pintype "power_in"))
      (node (ref "IC4") (pin "4") (pinfunction "GND1_4") (pintype "power_in"))
      (node (ref "IC5") (pin "4") (pinfunction "GND1_4") (pintype "power_in"))
      (node (ref "IC7") (pin "1") (pinfunction "IN-_1") (pintype "power_in"))
      (node (ref "IC8") (pin "2") (pinfunction "GND1.1_2") (pintype "power_in"))
      (node (ref "IC8") (pin "8") (pinfunction "GND1.2_8") (pintype "power_in"))
      (node (ref "IC9") (pin "2") (pinfunction "GND1_2") (pintype "power_in"))
      (node (ref "IC9") (pin "8") (pinfunction "GND1_8") (pintype "power_in"))
      (node (ref "JP7") (pin "1") (pinfunction "1_1") (pintype "passive"))
      (node (ref "LAN_IN") (pin "G-") (pinfunction "C-L_G-") (pintype "passive"))
      (node (ref "LAN_IN") (pin "M1") (pinfunction "SHIELD_M1") (pintype "input"))
      (node (ref "LAN_IN") (pin "M2") (pinfunction "SHIELD_M2") (pintype "input"))
      (node (ref "LAN_IN") (pin "Y-") (pinfunction "C-R_Y-") (pintype "passive"))
      (node (ref "LAN_PI") (pin "S@1") (pinfunction "S1_S@1") (pintype "passive"))
      (node (ref "LAN_PI") (pin "S@2") (pinfunction "S2_S@2") (pintype "passive"))
      (node (ref "R33") (pin "1") (pinfunction "1_1") (pintype "passive"))
      (node (ref "R34") (pin "1") (pinfunction "1_1") (pintype "passive"))
      (node (ref "R35") (pin "2") (pinfunction "2_2") (pintype "passive"))
      (node (ref "RPI") (pin "14") (pinfunction "14_14") (pintype "passive"))
      (node (ref "RPI") (pin "20") (pinfunction "20_20") (pintype "passive"))
      (node (ref "RPI") (pin "25") (pinfunction "25_25") (pintype "passive"))
      (node (ref "RPI") (pin "30") (pinfunction "30_30") (pintype "passive"))
      (node (ref "RPI") (pin "34") (pinfunction "34_34") (pintype "passive"))
      (node (ref "RPI") (pin "39") (pinfunction "39_39") (pintype "passive"))
      (node (ref "RPI") (pin "6") (pinfunction "6_6") (pintype "passive"))
      (node (ref "RPI") (pin "9") (pinfunction "9_9") (pintype "passive"))
      (node (ref "SV6") (pin "1") (pinfunction "1_1") (pintype "passive"))
      (node (ref "USB_PI") (pin "GND") (pinfunction "GND_GND") (pintype "bidirectional"))
      (node (ref "USB_PI") (pin "GND2") (pinfunction "S1_GND2") (pintype "bidirectional"))
      (node (ref "USB_PI") (pin "GND3") (pinfunction "S2_GND3") (pintype "bidirectional"))
    )
    (net (code "30") (name "GNDA") (class "Default")
      (node (ref "C10") (pin "2") (pinfunction "2_2") (pintype "passive"))
      (node (ref "C11") (pin "2") (pinfunction "2_2") (pintype "passive"))
      (node (ref "C12") (pin "2") (pinfunction "2_2") (pintype "passive"))
      (node (ref "C13") (pin "2") (pinfunction "2_2") (pintype "passive"))
      (node (ref "C14") (pin "2") (pinfunction "2_2") (pintype "passive"))
      (node (ref "C17") (pin "2") (pinfunction "2_2") (pintype "passive"))
      (node (ref "C18") (pin "2") (pinfunction "2_2") (pintype "passive"))
      (node (ref "C19") (pin "2") (pinfunction "2_2") (pintype "passive"))
      (node (ref "C2") (pin "2") (pinfunction "2_2") (pintype "passive"))
      (node (ref "C21") (pin "2") (pinfunction "2_2") (pintype "passive"))
      (node (ref "C24") (pin "2") (pinfunction "2_2") (pintype "passive"))
      (node (ref "C3") (pin "2") (pinfunction "2_2") (pintype "passive"))
      (node (ref "C34") (pin "2") (pinfunction "2_2") (pintype "passive"))
      (node (ref "C37") (pin "2") (pinfunction "2_2") (pintype "passive"))
      (node (ref "C38") (pin "2") (pinfunction "2_2") (pintype "passive"))
      (node (ref "C5") (pin "2") (pinfunction "2_2") (pintype "passive"))
      (node (ref "C6") (pin "2") (pinfunction "2_2") (pintype "passive"))
      (node (ref "C9") (pin "2") (pinfunction "2_2") (pintype "passive"))
      (node (ref "IC1") (pin "9") (pinfunction "GND2_9") (pintype "power_in"))
      (node (ref "IC10") (pin "15") (pinfunction "GND2_15") (pintype "power_in"))
      (node (ref "IC10") (pin "9") (pinfunction "GND2_9") (pintype "power_in"))
      (node (ref "IC11") (pin "15") (pinfunction "GND2_15") (pintype "power_in"))
      (node (ref "IC11") (pin "9") (pinfunction "GND2_9") (pintype "power_in"))
      (node (ref "IC15") (pin "2") (pinfunction "GND_2") (pintype "bidirectional"))
      (node (ref "IC16") (pin "1") (pinfunction "S_1") (pintype "passive"))
      (node (ref "IC2") (pin "2") (pinfunction "GND1_2") (pintype "power_in"))
      (node (ref "IC2") (pin "8") (pinfunction "GND1_8") (pintype "power_in"))
      (node (ref "IC3") (pin "2") (pinfunction "GND1_2") (pintype "power_in"))
      (node (ref "IC3") (pin "8") (pinfunction "GND1_8") (pintype "power_in"))
      (node (ref "IC4") (pin "5") (pinfunction "GND2_5") (pintype "power_in"))
      (node (ref "IC5") (pin "5") (pinfunction "GND2_5") (pintype "power_in"))
      (node (ref "IC6") (pin "10") (pinfunction "DGND_10") (pintype "power_in"))
      (node (ref "IC6") (pin "16") (pinfunction "RESET_16") (pintype "input"))
      (node (ref "IC6") (pin "17") (pinfunction "DAP_17") (pintype "bidirectional"))
      (node (ref "IC6") (pin "2") (pinfunction "REFG_2") (pintype "bidirectional"))
      (node (ref "IC6") (pin "4") (pinfunction "INCN_4") (pintype "input"))
      (node (ref "IC6") (pin "6") (pinfunction "INVG_6") (pintype "power_in"))
      (node (ref "IC6") (pin "7") (pinfunction "GND_7") (pintype "bidirectional"))
      (node (ref "IC7") (pin "7") (pinfunction "OUT-_7") (pintype "power_in"))
      (node (ref "IC8") (pin "15") (pinfunction "GND2.2_15") (pintype "power_in"))
      (node (ref "IC8") (pin "9") (pinfunction "GND2.1_9") (pintype "power_in"))
      (node (ref "IC9") (pin "15") (pinfunction "GND2_15") (pintype "power_in"))
      (node (ref "IC9") (pin "9") (pinfunction "GND2_9") (pintype "power_in"))
      (node (ref "JP8") (pin "1") (pinfunction "1_1") (pintype "passive"))
      (node (ref "R16") (pin "1") (pinfunction "1_1") (pintype "passive"))
      (node (ref "R6") (pin "1") (pinfunction "1_1") (pintype "passive"))
      (node (ref "R8") (pin "1") (pinfunction "1_1") (pintype "passive"))
      (node (ref "TP_IGND") (pin "MP") (pinfunction "MP_MP") (pintype "passive"))
      (node (ref "TP_IGND1") (pin "MP") (pinfunction "MP_MP") (pintype "passive"))
    )
    (net (code "31") (name "GSCL") (class "Default")
      (node (ref "IC12") (pin "6") (pinfunction "SCL_6") (pintype "input"))
      (node (ref "IC14") (pin "19") (pinfunction "19_SCL/SPI_CLK_19") (pintype "bidirectional"))
    )
    (net (code "32") (name "GSDA") (class "Default")
      (node (ref "IC12") (pin "5") (pinfunction "SDA_5") (pintype "bidirectional"))
      (node (ref "IC14") (pin "18") (pinfunction "18_SDA/SPI_CS_N_18") (pintype "bidirectional"))
    )
    (net (code "33") (name "INCP") (class "Default")
      (node (ref "C") (pin "2") (pinfunction "2_2") (pintype "passive"))
      (node (ref "IC6") (pin "3") (pinfunction "INCP_3") (pintype "input"))
      (node (ref "R16") (pin "2") (pinfunction "2_2") (pintype "passive"))
    )
    (net (code "34") (name "INVP") (class "Default")
      (node (ref "IC6") (pin "5") (pinfunction "INVP_5") (pintype "input"))
      (node (ref "R14") (pin "1") (pinfunction "1_1") (pintype "passive"))
      (node (ref "R8") (pin "2") (pinfunction "2_2") (pintype "passive"))
    )
    (net (code "35") (name "I_B1C1") (class "Default")
      (node (ref "GPIO") (pin "4") (pinfunction "4_4") (pintype "passive"))
      (node (ref "R2") (pin "2") (pinfunction "2_2") (pintype "passive"))
    )
    (net (code "36") (name "I_B1C2") (class "Default")
      (node (ref "GPIO") (pin "3") (pinfunction "3_3") (pintype "passive"))
      (node (ref "R3") (pin "2") (pinfunction "2_2") (pintype "passive"))
    )
    (net (code "37") (name "I_B1C3") (class "Default")
      (node (ref "GPIO") (pin "2") (pinfunction "2_2") (pintype "passive"))
      (node (ref "R4") (pin "2") (pinfunction "2_2") (pintype "passive"))
    )
    (net (code "38") (name "I_B1C4") (class "Default")
      (node (ref "GPIO") (pin "1") (pinfunction "1_1") (pintype "passive"))
      (node (ref "R5") (pin "2") (pinfunction "2_2") (pintype "passive"))
    )
    (net (code "39") (name "I_B2C1") (class "Default")
      (node (ref "GPIO") (pin "8") (pinfunction "8_8") (pintype "passive"))
      (node (ref "R25") (pin "2") (pinfunction "2_2") (pintype "passive"))
    )
    (net (code "40") (name "I_B2C2") (class "Default")
      (node (ref "GPIO") (pin "7") (pinfunction "7_7") (pintype "passive"))
      (node (ref "R26") (pin "2") (pinfunction "2_2") (pintype "passive"))
    )
    (net (code "41") (name "I_B2C3") (class "Default")
      (node (ref "GPIO") (pin "6") (pinfunction "6_6") (pintype "passive"))
      (node (ref "R27") (pin "2") (pinfunction "2_2") (pintype "passive"))
    )
    (net (code "42") (name "I_B2C4") (class "Default")
      (node (ref "GPIO") (pin "5") (pinfunction "5_5") (pintype "passive"))
      (node (ref "R28") (pin "2") (pinfunction "2_2") (pintype "passive"))
    )
    (net (code "43") (name "I_EN_BLOCK1") (class "Default")
      (node (ref "IC10") (pin "10") (pinfunction "EN_10") (pintype "input"))
      (node (ref "IC11") (pin "13") (pinfunction "OUTB_13") (pintype "output"))
    )
    (net (code "44") (name "I_EN_BLOCK2") (class "Default")
      (node (ref "IC11") (pin "12") (pinfunction "OUTC_12") (pintype "output"))
      (node (ref "IC9") (pin "10") (pinfunction "EN_10") (pintype "input"))
    )
    (net (code "45") (name "I_PWR_SW") (class "Default")
      (node (ref "IC11") (pin "14") (pinfunction "OUTA_14") (pintype "output"))
      (node (ref "R20") (pin "1") (pinfunction "1_1") (pintype "passive"))
      (node (ref "R6") (pin "2") (pinfunction "2_2") (pintype "passive"))
    )
    (net (code "46") (name "I_RST_SW") (class "Default")
      (node (ref "GPIO") (pin "9") (pinfunction "9_9") (pintype "passive"))
      (node (ref "IC11") (pin "11") (pinfunction "OUTD_11") (pintype "output"))
    )
    (net (code "47") (name "MISO") (class "Default")
      (node (ref "IC5") (pin "2") (pinfunction "OUTA_2") (pintype "output"))
      (node (ref "RPI") (pin "21") (pinfunction "21_21") (pintype "passive"))
    )
    (net (code "48") (name "MOSI") (class "Default")
      (node (ref "IC5") (pin "3") (pinfunction "INB_3") (pintype "input"))
      (node (ref "RPI") (pin "19") (pinfunction "19_19") (pintype "passive"))
    )
    (net (code "49") (name "Net-(C35-Pad1)") (class "Default")
      (node (ref "C35") (pin "1") (pinfunction "1_1") (pintype "passive"))
      (node (ref "L3") (pin "2") (pinfunction "2_2") (pintype "passive"))
      (node (ref "R38") (pin "1") (pinfunction "1_1") (pintype "passive"))
    )
    (net (code "50") (name "Net-(IC3-INA)") (class "Default")
      (node (ref "IC3") (pin "3") (pinfunction "INA_3") (pintype "input"))
      (node (ref "IC9") (pin "14") (pinfunction "OUTA_14") (pintype "output"))
      (node (ref "R25") (pin "1") (pinfunction "1_1") (pintype "passive"))
    )
    (net (code "51") (name "Net-(IC3-INB)") (class "Default")
      (node (ref "IC3") (pin "4") (pinfunction "INB_4") (pintype "input"))
      (node (ref "IC9") (pin "13") (pinfunction "OUTB_13") (pintype "output"))
      (node (ref "R26") (pin "1") (pinfunction "1_1") (pintype "passive"))
    )
    (net (code "52") (name "Net-(IC3-INC)") (class "Default")
      (node (ref "IC3") (pin "5") (pinfunction "INC_5") (pintype "input"))
      (node (ref "IC9") (pin "12") (pinfunction "OUTC_12") (pintype "output"))
      (node (ref "R27") (pin "1") (pinfunction "1_1") (pintype "passive"))
    )
    (net (code "53") (name "Net-(IC3-IND)") (class "Default")
      (node (ref "IC3") (pin "6") (pinfunction "IND_6") (pintype "input"))
      (node (ref "IC9") (pin "11") (pinfunction "OUTD_11") (pintype "output"))
      (node (ref "R28") (pin "1") (pinfunction "1_1") (pintype "passive"))
    )
    (net (code "54") (name "Net-(IC3-OUTA)") (class "Default")
      (node (ref "IC3") (pin "14") (pinfunction "OUTA_14") (pintype "output"))
      (node (ref "IC9") (pin "3") (pinfunction "INA_3") (pintype "input"))
      (node (ref "R32") (pin "1") (pinfunction "1_1") (pintype "passive"))
    )
    (net (code "55") (name "Net-(IC3-OUTB)") (class "Default")
      (node (ref "IC3") (pin "13") (pinfunction "OUTB_13") (pintype "output"))
      (node (ref "IC9") (pin "4") (pinfunction "INB_4") (pintype "input"))
      (node (ref "R31") (pin "1") (pinfunction "1_1") (pintype "passive"))
    )
    (net (code "56") (name "Net-(IC3-OUTC)") (class "Default")
      (node (ref "IC3") (pin "12") (pinfunction "OUTC_12") (pintype "output"))
      (node (ref "IC9") (pin "5") (pinfunction "INC_5") (pintype "input"))
      (node (ref "R30") (pin "1") (pinfunction "1_1") (pintype "passive"))
    )
    (net (code "57") (name "Net-(IC3-OUTD)") (class "Default")
      (node (ref "IC3") (pin "11") (pinfunction "OUTD_11") (pintype "output"))
      (node (ref "IC9") (pin "6") (pinfunction "IND_6") (pintype "input"))
      (node (ref "R29") (pin "1") (pinfunction "1_1") (pintype "passive"))
    )
    (net (code "58") (name "Net-(IC4-OUTA)") (class "Default")
      (node (ref "IC4") (pin "7") (pinfunction "OUTA_7") (pintype "output"))
      (node (ref "R15") (pin "2") (pinfunction "2_2") (pintype "passive"))
    )
    (net (code "59") (name "Net-(IC4-OUTB)") (class "Default")
      (node (ref "IC4") (pin "6") (pinfunction "OUTB_6") (pintype "output"))
      (node (ref "R17") (pin "2") (pinfunction "2_2") (pintype "passive"))
    )
    (net (code "60") (name "Net-(IC5-INA)") (class "Default")
      (node (ref "IC5") (pin "7") (pinfunction "INA_7") (pintype "input"))
      (node (ref "R18") (pin "2") (pinfunction "2_2") (pintype "passive"))
    )
    (net (code "61") (name "Net-(IC5-OUTB)") (class "Default")
      (node (ref "IC5") (pin "6") (pinfunction "OUTB_6") (pintype "output"))
      (node (ref "R19") (pin "2") (pinfunction "2_2") (pintype "passive"))
    )
    (net (code "62") (name "Net-(IC6-REFC)") (class "Default")
      (node (ref "C10") (pin "1") (pinfunction "1_1") (pintype "passive"))
      (node (ref "IC6") (pin "1") (pinfunction "REFC_1") (pintype "bidirectional"))
    )
    (net (code "63") (name "Net-(IC7-IN+)") (class "Default")
      (node (ref "IC7") (pin "3") (pinfunction "IN+_3") (pintype "power_in"))
      (node (ref "L1") (pin "P$2") (pinfunction "2_P$2") (pintype "passive"))
    )
    (net (code "64") (name "Net-(IC7-OUT+)") (class "Default")
      (node (ref "IC7") (pin "8") (pinfunction "OUT+_8") (pintype "power_in"))
      (node (ref "L2") (pin "P$1") (pinfunction "1_P$1") (pintype "passive"))
    )
    (net (code "65") (name "Net-(IC10-INA)") (class "Default")
      (node (ref "IC10") (pin "3") (pinfunction "INA_3") (pintype "input"))
      (node (ref "IC2") (pin "14") (pinfunction "OUTA_14") (pintype "output"))
      (node (ref "R24") (pin "1") (pinfunction "1_1") (pintype "passive"))
    )
    (net (code "66") (name "Net-(IC10-INB)") (class "Default")
      (node (ref "IC10") (pin "4") (pinfunction "INB_4") (pintype "input"))
      (node (ref "IC2") (pin "13") (pinfunction "OUTB_13") (pintype "output"))
      (node (ref "R23") (pin "1") (pinfunction "1_1") (pintype "passive"))
    )
    (net (code "67") (name "Net-(IC10-INC)") (class "Default")
      (node (ref "IC10") (pin "5") (pinfunction "INC_5") (pintype "input"))
      (node (ref "IC2") (pin "12") (pinfunction "OUTC_12") (pintype "output"))
      (node (ref "R22") (pin "1") (pinfunction "1_1") (pintype "passive"))
    )
    (net (code "68") (name "Net-(IC10-IND)") (class "Default")
      (node (ref "IC10") (pin "6") (pinfunction "IND_6") (pintype "input"))
      (node (ref "IC2") (pin "11") (pinfunction "OUTD_11") (pintype "output"))
      (node (ref "R21") (pin "1") (pinfunction "1_1") (pintype "passive"))
    )
    (net (code "69") (name "Net-(IC10-OUTA)") (class "Default")
      (node (ref "IC10") (pin "14") (pinfunction "OUTA_14") (pintype "output"))
      (node (ref "IC2") (pin "3") (pinfunction "INA_3") (pintype "input"))
      (node (ref "R2") (pin "1") (pinfunction "1_1") (pintype "passive"))
    )
    (net (code "70") (name "Net-(IC10-OUTB)") (class "Default")
      (node (ref "IC10") (pin "13") (pinfunction "OUTB_13") (pintype "output"))
      (node (ref "IC2") (pin "4") (pinfunction "INB_4") (pintype "input"))
      (node (ref "R3") (pin "1") (pinfunction "1_1") (pintype "passive"))
    )
    (net (code "71") (name "Net-(IC10-OUTC)") (class "Default")
      (node (ref "IC10") (pin "12") (pinfunction "OUTC_12") (pintype "output"))
      (node (ref "IC2") (pin "5") (pinfunction "INC_5") (pintype "input"))
      (node (ref "R4") (pin "1") (pinfunction "1_1") (pintype "passive"))
    )
    (net (code "72") (name "Net-(IC10-OUTD)") (class "Default")
      (node (ref "IC10") (pin "11") (pinfunction "OUTD_11") (pintype "output"))
      (node (ref "IC2") (pin "6") (pinfunction "IND_6") (pintype "input"))
      (node (ref "R5") (pin "1") (pinfunction "1_1") (pintype "passive"))
    )
    (net (code "73") (name "Net-(IC14-8_RESET_N)") (class "Default")
      (node (ref "IC14") (pin "8") (pinfunction "8_RESET_N_8") (pintype "bidirectional"))
      (node (ref "IC14") (pin "9") (pinfunction "9_VCC_RF_9") (pintype "bidirectional"))
      (node (ref "R38") (pin "2") (pinfunction "2_2") (pintype "passive"))
    )
    (net (code "74") (name "Net-(IC14-11_RF_IN)") (class "Default")
      (node (ref "GPS_ANT") (pin "1") (pinfunction "1_1") (pintype "passive"))
      (node (ref "IC14") (pin "11") (pinfunction "11_RF_IN_11") (pintype "bidirectional"))
      (node (ref "L3") (pin "1") (pinfunction "1_1") (pintype "passive"))
    )
    (net (code "75") (name "Net-(IC16A-D)") (class "Default")
      (node (ref "IC16") (pin "6") (pinfunction "D_6") (pintype "passive"))
      (node (ref "R7") (pin "1") (pinfunction "1_1") (pintype "passive"))
    )
    (net (code "76") (name "Net-(IC16A-G)") (class "Default")
      (node (ref "IC16") (pin "2") (pinfunction "G_2") (pintype "passive"))
      (node (ref "R20") (pin "2") (pinfunction "2_2") (pintype "passive"))
    )
    (net (code "77") (name "Net-(IC16B-G)") (class "Default")
      (node (ref "IC16") (pin "5") (pinfunction "G_5") (pintype "passive"))
      (node (ref "R7") (pin "2") (pinfunction "2_2") (pintype "passive"))
      (node (ref "R9") (pin "1") (pinfunction "1_1") (pintype "passive"))
    )
    (net (code "78") (name "Net-(LAN_IN-A-L)") (class "Default")
      (node (ref "LAN_IN") (pin "G+") (pinfunction "A-L_G+") (pintype "passive"))
      (node (ref "R37") (pin "2") (pinfunction "2_2") (pintype "passive"))
    )
    (net (code "79") (name "Net-(LAN_IN-A-R)") (class "Default")
      (node (ref "LAN_IN") (pin "Y+") (pinfunction "A-R_Y+") (pintype "passive"))
      (node (ref "R36") (pin "2") (pinfunction "2_2") (pintype "passive"))
    )
    (net (code "80") (name "Net-(R10-Pad2)") (class "Default")
      (node (ref "R10") (pin "2") (pinfunction "2_2") (pintype "passive"))
      (node (ref "USB_PI") (pin "D+") (pinfunction "D+_D+") (pintype "bidirectional"))
    )
    (net (code "81") (name "Net-(R11-Pad2)") (class "Default")
      (node (ref "R11") (pin "2") (pinfunction "2_2") (pintype "passive"))
      (node (ref "USB_PI") (pin "D-") (pinfunction "D-_D-") (pintype "bidirectional"))
    )
    (net (code "82") (name "Net-(R12-Pad2)") (class "Default")
      (node (ref "R12") (pin "2") (pinfunction "2_2") (pintype "passive"))
      (node (ref "USB_TGT") (pin "2") (pinfunction "2_2") (pintype "passive"))
    )
    (net (code "83") (name "Net-(R13-Pad2)") (class "Default")
      (node (ref "R13") (pin "2") (pinfunction "2_2") (pintype "passive"))
      (node (ref "USB_TGT") (pin "3") (pinfunction "3_3") (pintype "passive"))
    )
    (net (code "84") (name "Net-(R14-Pad2)") (class "Default")
      (node (ref "R14") (pin "2") (pinfunction "2_2") (pintype "passive"))
      (node (ref "V") (pin "2") (pinfunction "2_2") (pintype "passive"))
    )
    (net (code "85") (name "OADJ") (class "Default")
      (node (ref "R35") (pin "1") (pinfunction "1_1") (pintype "passive"))
      (node (ref "SV6") (pin "3") (pinfunction "3_3") (pintype "passive"))
    )
    (net (code "86") (name "PPS") (class "Default")
      (node (ref "IC14") (pin "3") (pinfunction "3_TIMEPULSE_3") (pintype "bidirectional"))
      (node (ref "RPI") (pin "37") (pinfunction "37_37") (pintype "passive"))
    )
    (net (code "87") (name "PWR_SW") (class "Default")
      (node (ref "IC11") (pin "3") (pinfunction "INA_3") (pintype "input"))
      (node (ref "RPI") (pin "40") (pinfunction "40_40") (pintype "passive"))
    )
    (net (code "88") (name "RST_SW") (class "Default")
      (node (ref "IC11") (pin "6") (pinfunction "IND_6") (pintype "input"))
      (node (ref "RPI") (pin "38") (pinfunction "38_38") (pintype "passive"))
    )
    (net (code "89") (name "RX+") (class "Default")
      (node (ref "LAN_IN") (pin "4") (pinfunction "RD+_4") (pintype "input"))
      (node (ref "LAN_PI") (pin "3") (pinfunction "3_3") (pintype "passive"))
    )
    (net (code "90") (name "RX-") (class "Default")
      (node (ref "LAN_IN") (pin "5") (pinfunction "RD-_5") (pintype "input"))
      (node (ref "LAN_PI") (pin "6") (pinfunction "6_6") (pintype "passive"))
    )
    (net (code "91") (name "RXD") (class "Default")
      (node (ref "IC14") (pin "20") (pinfunction "20_TXD/SPI_MISO_20") (pintype "bidirectional"))
      (node (ref "RPI") (pin "10") (pinfunction "10_10") (pintype "passive"))
    )
    (net (code "92") (name "SCL") (class "Default")
      (node (ref "IC1") (pin "6") (pinfunction "ASCL_6") (pintype "input"))
      (node (ref "IC13") (pin "6") (pinfunction "SCL_6") (pintype "bidirectional"))
      (node (ref "RPI") (pin "5") (pinfunction "5_5") (pintype "passive"))
    )
    (net (code "93") (name "SCLK") (class "Default")
      (node (ref "IC4") (pin "2") (pinfunction "INA_2") (pintype "input"))
      (node (ref "RPI") (pin "23") (pinfunction "23_23") (pintype "passive"))
    )
    (net (code "94") (name "SDA") (class "Default")
      (node (ref "IC1") (pin "3") (pinfunction "ASDA_3") (pintype "bidirectional"))
      (node (ref "IC13") (pin "5") (pinfunction "SDA_5") (pintype "bidirectional"))
      (node (ref "RPI") (pin "3") (pinfunction "3_3") (pintype "passive"))
    )
    (net (code "95") (name "SPD") (class "Default")
      (node (ref "IC8") (pin "13") (pinfunction "SPD_13") (pintype "input"))
      (node (ref "JP8") (pin "2") (pinfunction "2_2") (pintype "passive"))
    )
    (net (code "96") (name "SPU") (class "Default")
      (node (ref "IC8") (pin "5") (pinfunction "SPU_5") (pintype "input"))
      (node (ref "JP7") (pin "2") (pinfunction "2_2") (pintype "passive"))
    )
    (net (code "97") (name "TX+") (class "Default")
      (node (ref "LAN_IN") (pin "1") (pinfunction "TD+_1") (pintype "input"))
      (node (ref "LAN_PI") (pin "1") (pinfunction "1_1") (pintype "passive"))
    )
    (net (code "98") (name "TX-") (class "Default")
      (node (ref "LAN_IN") (pin "3") (pinfunction "TD-_3") (pintype "input"))
      (node (ref "LAN_PI") (pin "2") (pinfunction "2_2") (pintype "passive"))
    )
    (net (code "99") (name "TXD") (class "Default")
      (node (ref "IC14") (pin "21") (pinfunction "21_RXD/SPI_MOSI_21") (pintype "bidirectional"))
      (node (ref "RPI") (pin "8") (pinfunction "8_8") (pintype "passive"))
    )
    (net (code "100") (name "USB_D+") (class "Default")
      (node (ref "IC8") (pin "7") (pinfunction "UD+_7") (pintype "bidirectional"))
      (node (ref "R10") (pin "1") (pinfunction "1_1") (pintype "passive"))
    )
    (net (code "101") (name "USB_D-") (class "Default")
      (node (ref "IC8") (pin "6") (pinfunction "UD-_6") (pintype "bidirectional"))
      (node (ref "R11") (pin "1") (pinfunction "1_1") (pintype "passive"))
    )
    (net (code "102") (name "V-") (class "Default")
      (node (ref "C") (pin "1") (pinfunction "1_1") (pintype "passive"))
      (node (ref "USB_TGT") (pin "4") (pinfunction "4_4") (pintype "passive"))
    )
    (net (code "103") (name "VBUS") (class "Default")
      (node (ref "5V") (pin "2") (pinfunction "2_2") (pintype "passive"))
      (node (ref "C4") (pin "1") (pinfunction "1_1") (pintype "passive"))
      (node (ref "C8") (pin "1") (pinfunction "1_1") (pintype "passive"))
      (node (ref "IC8") (pin "1") (pinfunction "VBUS1_1") (pintype "power_in"))
      (node (ref "L1") (pin "P$1") (pinfunction "1_P$1") (pintype "passive"))
      (node (ref "USB_PI") (pin "VBUS") (pinfunction "VBUS_VBUS") (pintype "bidirectional"))
    )
    (net (code "104") (name "VCC") (class "Default")
      (node (ref "C11") (pin "1") (pinfunction "1_1") (pintype "passive"))
      (node (ref "C12") (pin "1") (pinfunction "1_1") (pintype "passive"))
      (node (ref "C13") (pin "1") (pinfunction "1_1") (pintype "passive"))
      (node (ref "C14") (pin "1") (pinfunction "1_1") (pintype "passive"))
      (node (ref "C17") (pin "1") (pinfunction "1_1") (pintype "passive"))
      (node (ref "C18") (pin "1") (pinfunction "1_1") (pintype "passive"))
      (node (ref "C19") (pin "1") (pinfunction "1_1") (pintype "passive"))
      (node (ref "C37") (pin "1") (pinfunction "1_1") (pintype "passive"))
      (node (ref "C6") (pin "1") (pinfunction "1_1") (pintype "passive"))
      (node (ref "IC15") (pin "1") (pinfunction "VIN_1") (pintype "bidirectional"))
      (node (ref "IC15") (pin "3") (pinfunction "EN_3") (pintype "bidirectional"))
      (node (ref "IC16") (pin "4") (pinfunction "S_4") (pintype "passive"))
      (node (ref "IC4") (pin "8") (pinfunction "VCC2_8") (pintype "power_in"))
      (node (ref "IC5") (pin "8") (pinfunction "VCC2_8") (pintype "power_in"))
      (node (ref "IC6") (pin "8") (pinfunction "VDD_8") (pintype "power_in"))
      (node (ref "IC6") (pin "9") (pinfunction "VDIG_9") (pintype "power_in"))
      (node (ref "IC8") (pin "16") (pinfunction "VBUS2_16") (pintype "power_in"))
      (node (ref "L2") (pin "P$2") (pinfunction "2_P$2") (pintype "passive"))
      (node (ref "R9") (pin "2") (pinfunction "2_2") (pintype "passive"))
    )
    (net (code "105") (name "VCC_SW") (class "Default")
      (node (ref "IC16") (pin "3") (pinfunction "D_3") (pintype "passive"))
      (node (ref "TP_VCC") (pin "MP") (pinfunction "MP_MP") (pintype "passive"))
      (node (ref "USB_TGT") (pin "1") (pinfunction "1_1") (pintype "passive"))
      (node (ref "V") (pin "1") (pinfunction "1_1") (pintype "passive"))
    )
    (net (code "106") (name "VCC{slash}2") (class "Default")
      (node (ref "C2") (pin "1") (pinfunction "1_1") (pintype "passive"))
      (node (ref "C21") (pin "1") (pinfunction "1_1") (pintype "passive"))
      (node (ref "C24") (pin "1") (pinfunction "1_1") (pintype "passive"))
      (node (ref "C3") (pin "1") (pinfunction "1_1") (pintype "passive"))
      (node (ref "C34") (pin "1") (pinfunction "1_1") (pintype "passive"))
      (node (ref "C38") (pin "1") (pinfunction "1_1") (pintype "passive"))
      (node (ref "C5") (pin "1") (pinfunction "1_1") (pintype "passive"))
      (node (ref "IC1") (pin "16") (pinfunction "VCC2_16") (pintype "power_in"))
      (node (ref "IC10") (pin "16") (pinfunction "VCC2_16") (pintype "power_in"))
      (node (ref "IC11") (pin "10") (pinfunction "EN_10") (pintype "input"))
      (node (ref "IC11") (pin "16") (pinfunction "VCC2_16") (pintype "power_in"))
      (node (ref "IC15") (pin "5") (pinfunction "VOUT_5") (pintype "bidirectional"))
      (node (ref "IC2") (pin "1") (pinfunction "VCC1_1") (pintype "power_in"))
      (node (ref "IC3") (pin "1") (pinfunction "VCC1_1") (pintype "power_in"))
      (node (ref "IC9") (pin "16") (pinfunction "VCC2_16") (pintype "power_in"))
      (node (ref "R40") (pin "2") (pinfunction "2_2") (pintype "passive"))
      (node (ref "R41") (pin "2") (pinfunction "2_2") (pintype "passive"))
      (node (ref "TP_3V3") (pin "MP") (pinfunction "MP_MP") (pintype "passive"))
    )
    (net (code "107") (name "VDD1") (class "Default")
      (node (ref "C7") (pin "1") (pinfunction "1_1") (pintype "passive"))
      (node (ref "IC8") (pin "3") (pinfunction "VDD1_3") (pintype "power_in"))
      (node (ref "IC8") (pin "4") (pinfunction "PDEN_4") (pintype "input"))
      (node (ref "JP7") (pin "3") (pinfunction "3_3") (pintype "passive"))
    )
    (net (code "108") (name "VDD2") (class "Default")
      (node (ref "C9") (pin "1") (pinfunction "1_1") (pintype "passive"))
      (node (ref "IC8") (pin "12") (pinfunction "PIN_12") (pintype "input"))
      (node (ref "IC8") (pin "14") (pinfunction "VDD2_14") (pintype "power_in"))
      (node (ref "JP8") (pin "3") (pinfunction "3_3") (pintype "passive"))
    )
    (net (code "109") (name "VINA+") (class "Default")
      (node (ref "LAN_IN") (pin "10") (pinfunction "VC2+_10") (pintype "input"))
      (node (ref "POE") (pin "2") (pinfunction "2_2") (pintype "bidirectional"))
      (node (ref "SV5") (pin "1") (pinfunction "1_1") (pintype "passive"))
    )
    (net (code "110") (name "VINA-") (class "Default")
      (node (ref "LAN_IN") (pin "11") (pinfunction "VC2-_11") (pintype "input"))
      (node (ref "POE") (pin "1") (pinfunction "1_1") (pintype "bidirectional"))
      (node (ref "SV5") (pin "2") (pinfunction "2_2") (pintype "passive"))
    )
    (net (code "111") (name "VINB+") (class "Default")
      (node (ref "LAN_IN") (pin "8") (pinfunction "VC1+_8") (pintype "input"))
      (node (ref "POE") (pin "4") (pinfunction "4_4") (pintype "bidirectional"))
      (node (ref "SV5") (pin "3") (pinfunction "3_3") (pintype "passive"))
    )
    (net (code "112") (name "VINB-") (class "Default")
      (node (ref "LAN_IN") (pin "9") (pinfunction "VC1-_9") (pintype "input"))
      (node (ref "POE") (pin "3") (pinfunction "3_3") (pintype "bidirectional"))
      (node (ref "SV5") (pin "4") (pinfunction "4_4") (pintype "passive"))
    )
    (net (code "113") (name "unconnected-(IC1-NC-Pad2)") (class "Default")
      (node (ref "IC1") (pin "2") (pinfunction "NC_2") (pintype "no_connect"))
    )
    (net (code "114") (name "unconnected-(IC1-NC-Pad7)") (class "Default")
      (node (ref "IC1") (pin "7") (pinfunction "NC_7") (pintype "no_connect"))
    )
    (net (code "115") (name "unconnected-(IC1-NC-Pad10)") (class "Default")
      (node (ref "IC1") (pin "10") (pinfunction "NC_10") (pintype "no_connect"))
    )
    (net (code "116") (name "unconnected-(IC1-NC-Pad15)") (class "Default")
      (node (ref "IC1") (pin "15") (pinfunction "NC_15") (pintype "no_connect"))
    )
    (net (code "117") (name "unconnected-(IC2-NC-Pad7)") (class "Default")
      (node (ref "IC2") (pin "7") (pinfunction "NC_7") (pintype "no_connect"))
    )
    (net (code "118") (name "unconnected-(IC3-NC-Pad7)") (class "Default")
      (node (ref "IC3") (pin "7") (pinfunction "NC_7") (pintype "no_connect"))
    )
    (net (code "119") (name "unconnected-(IC6-RESERVED-Pad15)") (class "Default")
      (node (ref "IC6") (pin "15") (pinfunction "RESERVED_15") (pintype "no_connect"))
    )
    (net (code "120") (name "unconnected-(IC9-NC-Pad7)") (class "Default")
      (node (ref "IC9") (pin "7") (pinfunction "NC_7") (pintype "no_connect"))
    )
    (net (code "121") (name "unconnected-(IC10-NC-Pad7)") (class "Default")
      (node (ref "IC10") (pin "7") (pinfunction "NC_7") (pintype "no_connect"))
    )
    (net (code "122") (name "unconnected-(IC11-NC-Pad7)") (class "Default")
      (node (ref "IC11") (pin "7") (pinfunction "NC_7") (pintype "no_connect"))
    )
    (net (code "123") (name "unconnected-(IC13-WP-Pad7)") (class "Default")
      (node (ref "IC13") (pin "7") (pinfunction "WP_7") (pintype "bidirectional"))
    )
    (net (code "124") (name "unconnected-(IC14-1_SAFEBOOT_N-Pad1)") (class "Default")
      (node (ref "IC14") (pin "1") (pinfunction "1_SAFEBOOT_N_1") (pintype "bidirectional"))
    )
    (net (code "125") (name "unconnected-(IC14-2_D_SEL-Pad2)") (class "Default")
      (node (ref "IC14") (pin "2") (pinfunction "2_D_SEL_2") (pintype "bidirectional"))
    )
    (net (code "126") (name "unconnected-(IC14-4_EXTINT-Pad4)") (class "Default")
      (node (ref "IC14") (pin "4") (pinfunction "4_EXTINT_4") (pintype "bidirectional"))
    )
    (net (code "127") (name "unconnected-(IC14-5_USB_DM-Pad5)") (class "Default")
      (node (ref "IC14") (pin "5") (pinfunction "5_USB_DM_5") (pintype "bidirectional"))
    )
    (net (code "128") (name "unconnected-(IC14-6_USB_DP-Pad6)") (class "Default")
      (node (ref "IC14") (pin "6") (pinfunction "6_USB_DP_6") (pintype "bidirectional"))
    )
    (net (code "129") (name "unconnected-(IC14-14_LNA_EN{slash}RESERVED-Pad14)") (class "Default")
      (node (ref "IC14") (pin "14") (pinfunction "14_LNA_EN/RESERVED_14") (pintype "bidirectional"))
    )
    (net (code "130") (name "unconnected-(IC14-15_RESERVED-Pad15)") (class "Default")
      (node (ref "IC14") (pin "15") (pinfunction "15_RESERVED_15") (pintype "bidirectional"))
    )
    (net (code "131") (name "unconnected-(IC14-16_RESERVED-Pad16)") (class "Default")
      (node (ref "IC14") (pin "16") (pinfunction "16_RESERVED_16") (pintype "bidirectional"))
    )
    (net (code "132") (name "unconnected-(IC14-17_RESERVED-Pad17)") (class "Default")
      (node (ref "IC14") (pin "17") (pinfunction "17_RESERVED_17") (pintype "bidirectional"))
    )
    (net (code "133") (name "unconnected-(IC17-NC-Pad1)") (class "Default")
      (node (ref "IC17") (pin "1") (pinfunction "NC_1") (pintype "bidirectional"))
    )
    (net (code "134") (name "unconnected-(IC18-NC-Pad1)") (class "Default")
      (node (ref "IC18") (pin "1") (pinfunction "NC_1") (pintype "bidirectional"))
    )
    (net (code "135") (name "unconnected-(LAN_PI-Pad4)") (class "Default")
      (node (ref "LAN_PI") (pin "4") (pinfunction "4_4") (pintype "passive"))
    )
    (net (code "136") (name "unconnected-(LAN_PI-Pad5)") (class "Default")
      (node (ref "LAN_PI") (pin "5") (pinfunction "5_5") (pintype "passive"))
    )
    (net (code "137") (name "unconnected-(LAN_PI-Pad7)") (class "Default")
      (node (ref "LAN_PI") (pin "7") (pinfunction "7_7") (pintype "passive"))
    )
    (net (code "138") (name "unconnected-(LAN_PI-Pad8)") (class "Default")
      (node (ref "LAN_PI") (pin "8") (pinfunction "8_8") (pintype "passive"))
    )
    (net (code "139") (name "unconnected-(RPI-Pad26)") (class "Default")
      (node (ref "RPI") (pin "26") (pinfunction "26_26") (pintype "passive"))
    )
    (net (code "140") (name "unconnected-(RPI-Pad27)") (class "Default")
      (node (ref "RPI") (pin "27") (pinfunction "27_27") (pintype "passive"))
    )
    (net (code "141") (name "unconnected-(RPI-Pad28)") (class "Default")
      (node (ref "RPI") (pin "28") (pinfunction "28_28") (pintype "passive"))
    )
    (net (code "142") (name "unconnected-(RPI-Pad29)") (class "Default")
      (node (ref "RPI") (pin "29") (pinfunction "29_29") (pintype "passive"))
    )
    (net (code "143") (name "unconnected-(RPI-Pad31)") (class "Default")
      (node (ref "RPI") (pin "31") (pinfunction "31_31") (pintype "passive"))
    )
    (net (code "144") (name "unconnected-(RPI-Pad33)") (class "Default")
      (node (ref "RPI") (pin "33") (pinfunction "33_33") (pintype "passive"))
    )
    (net (code "145") (name "unconnected-(RPI-Pad35)") (class "Default")
      (node (ref "RPI") (pin "35") (pinfunction "35_35") (pintype "passive"))
    )
    (net (code "146") (name "unconnected-(SV6-Pad4)") (class "Default")
      (node (ref "SV6") (pin "4") (pinfunction "4_4") (pintype "passive"))
    )
    (net (code "147") (name "unconnected-(USB_TGT-PadS1)") (class "Default")
      (node (ref "USB_TGT") (pin "S1") (pinfunction "S1_S1") (pintype "passive"))
    )
    (net (code "148") (name "unconnected-(USB_TGT-PadS2)") (class "Default")
      (node (ref "USB_TGT") (pin "S2") (pinfunction "S2_S2") (pintype "passive"))
    )
    (net (code "149") (name "~{EN_BLOCK1}") (class "Default")
      (node (ref "IC17") (pin "4") (pinfunction "Y_4") (pintype "bidirectional"))
      (node (ref "IC2") (pin "10") (pinfunction "EN_10") (pintype "input"))
    )
    (net (code "150") (name "~{EN_BLOCK2}") (class "Default")
      (node (ref "IC18") (pin "4") (pinfunction "Y_4") (pintype "bidirectional"))
      (node (ref "IC3") (pin "10") (pinfunction "EN_10") (pintype "input"))
    )
  )
)
